# VCFAA_v2.net
KiCad netlist of a schematic drawn in EAGLE
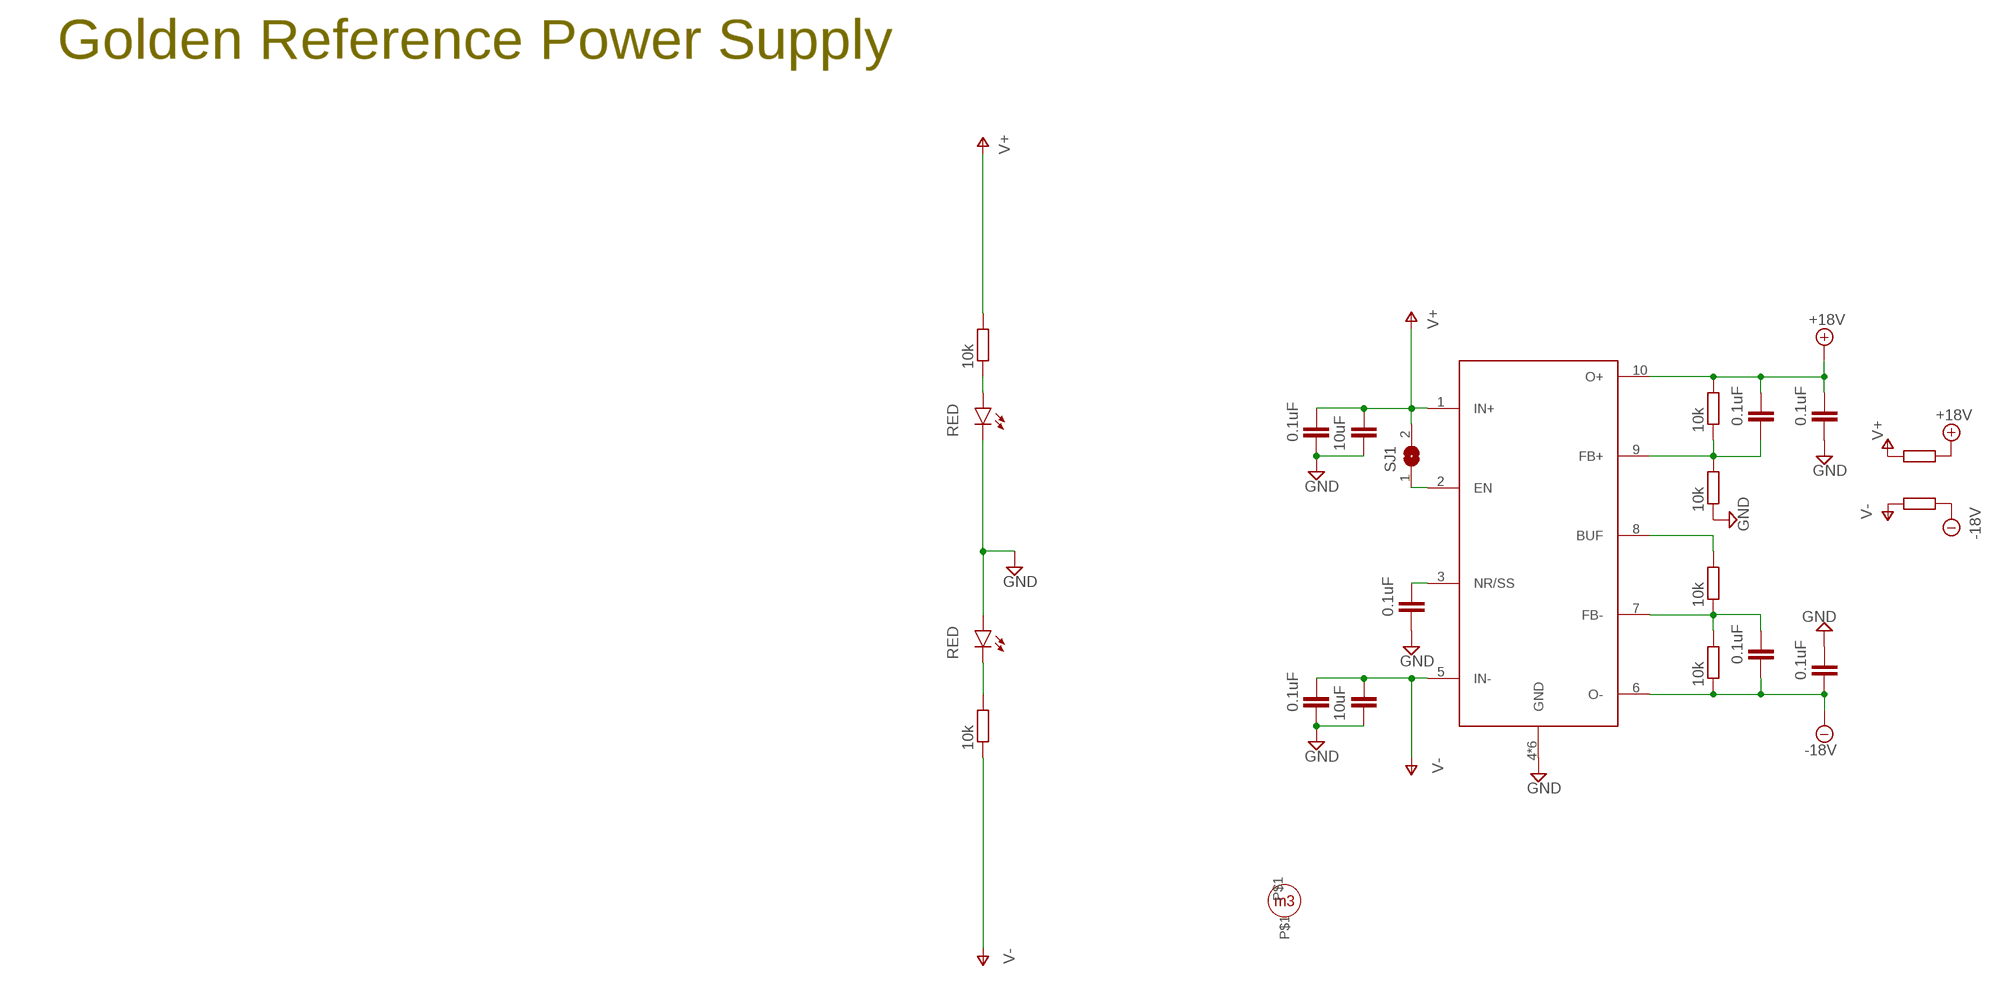
[diagram p0: schematic, sheet 1]
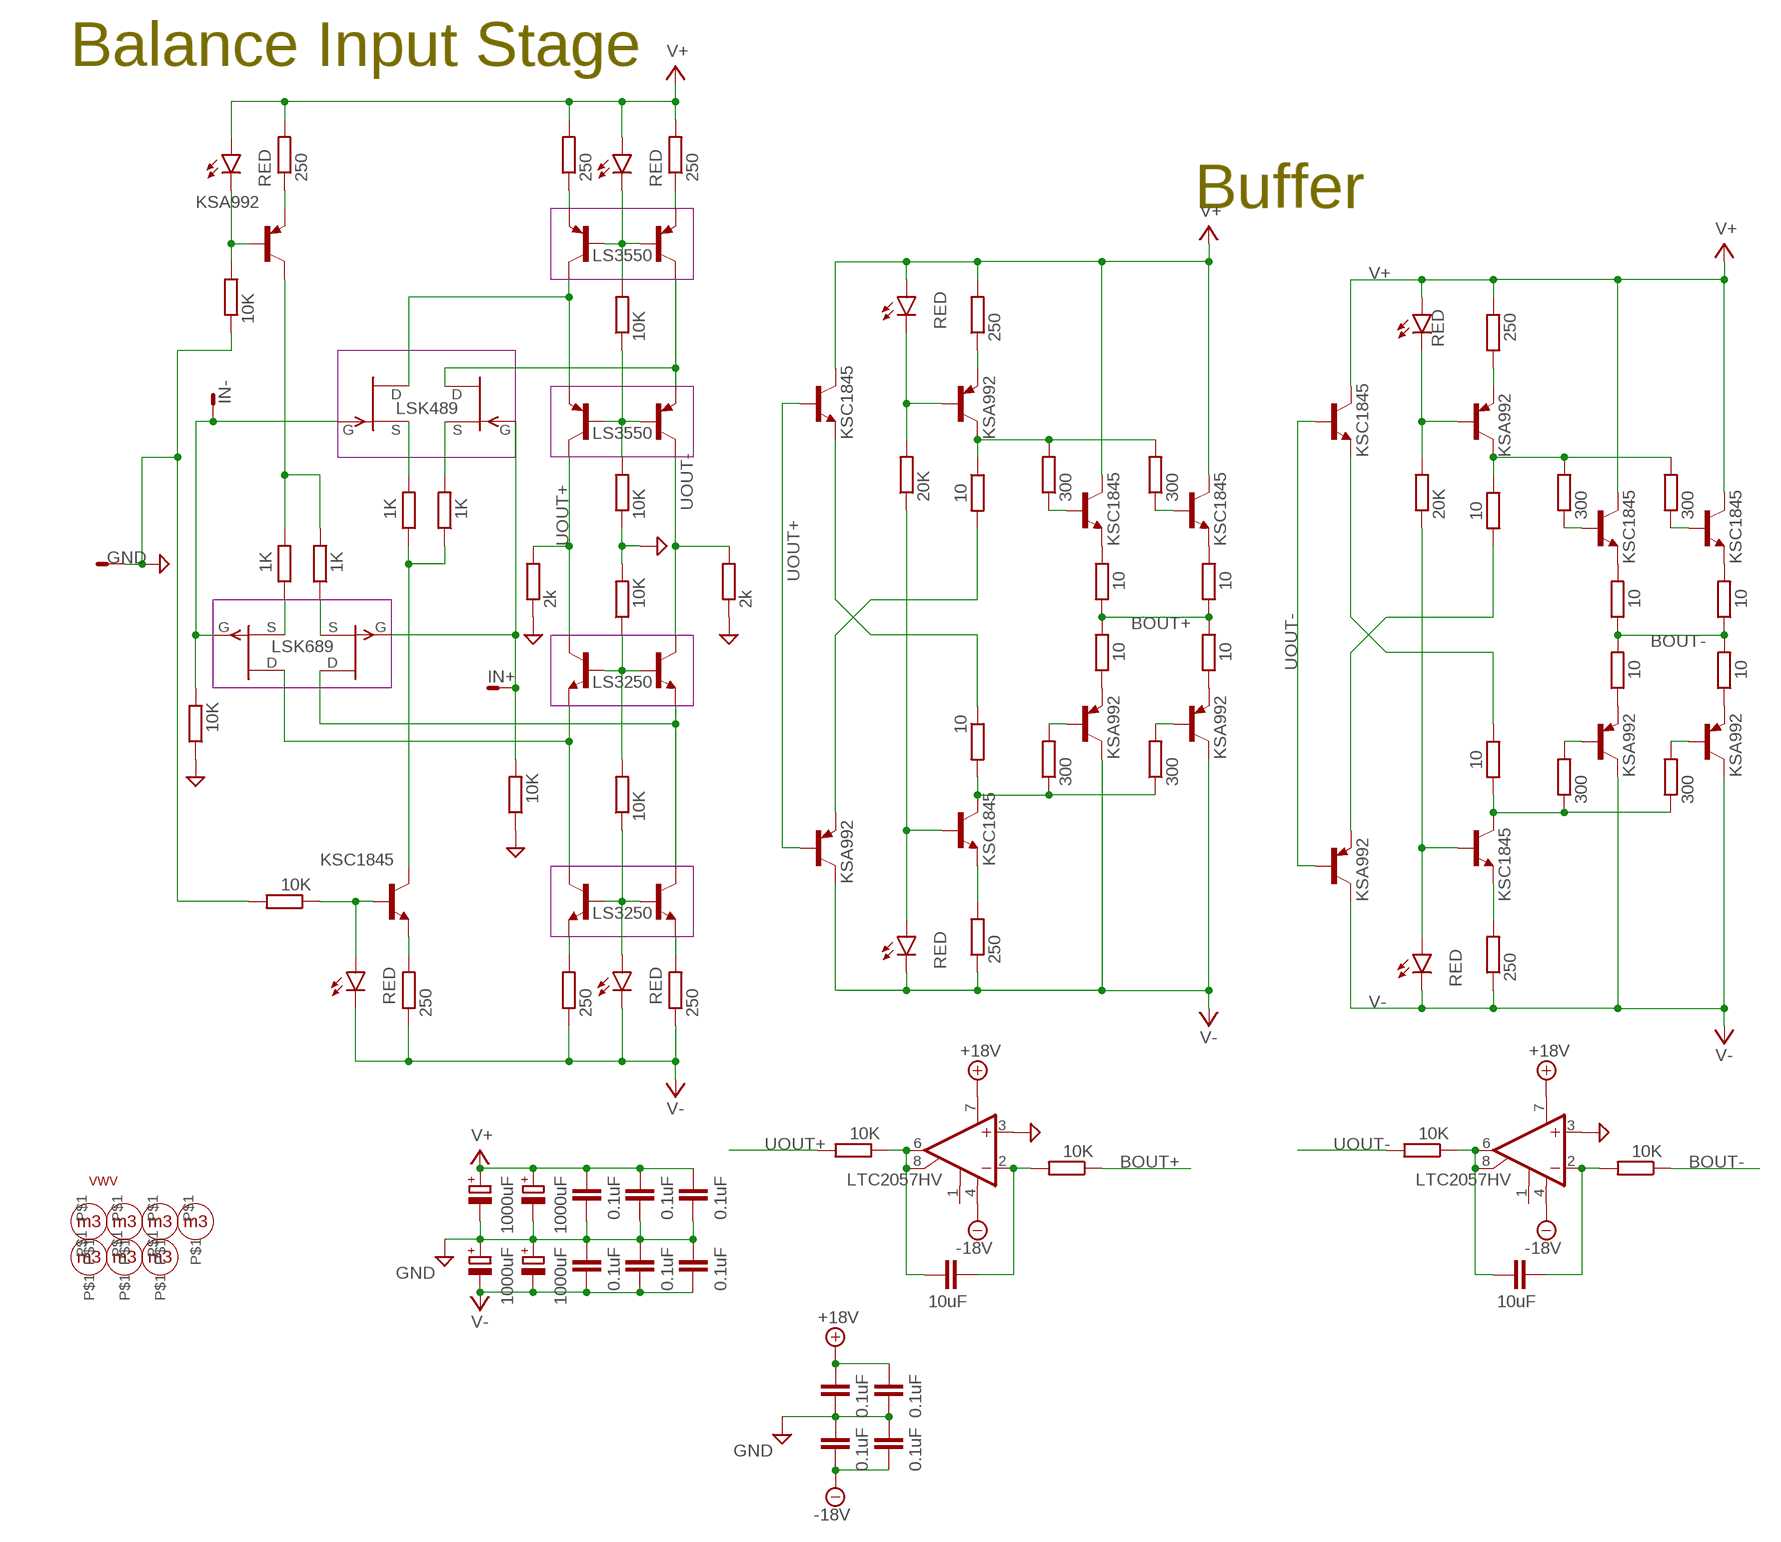
[diagram p1: schematic, sheet 2]
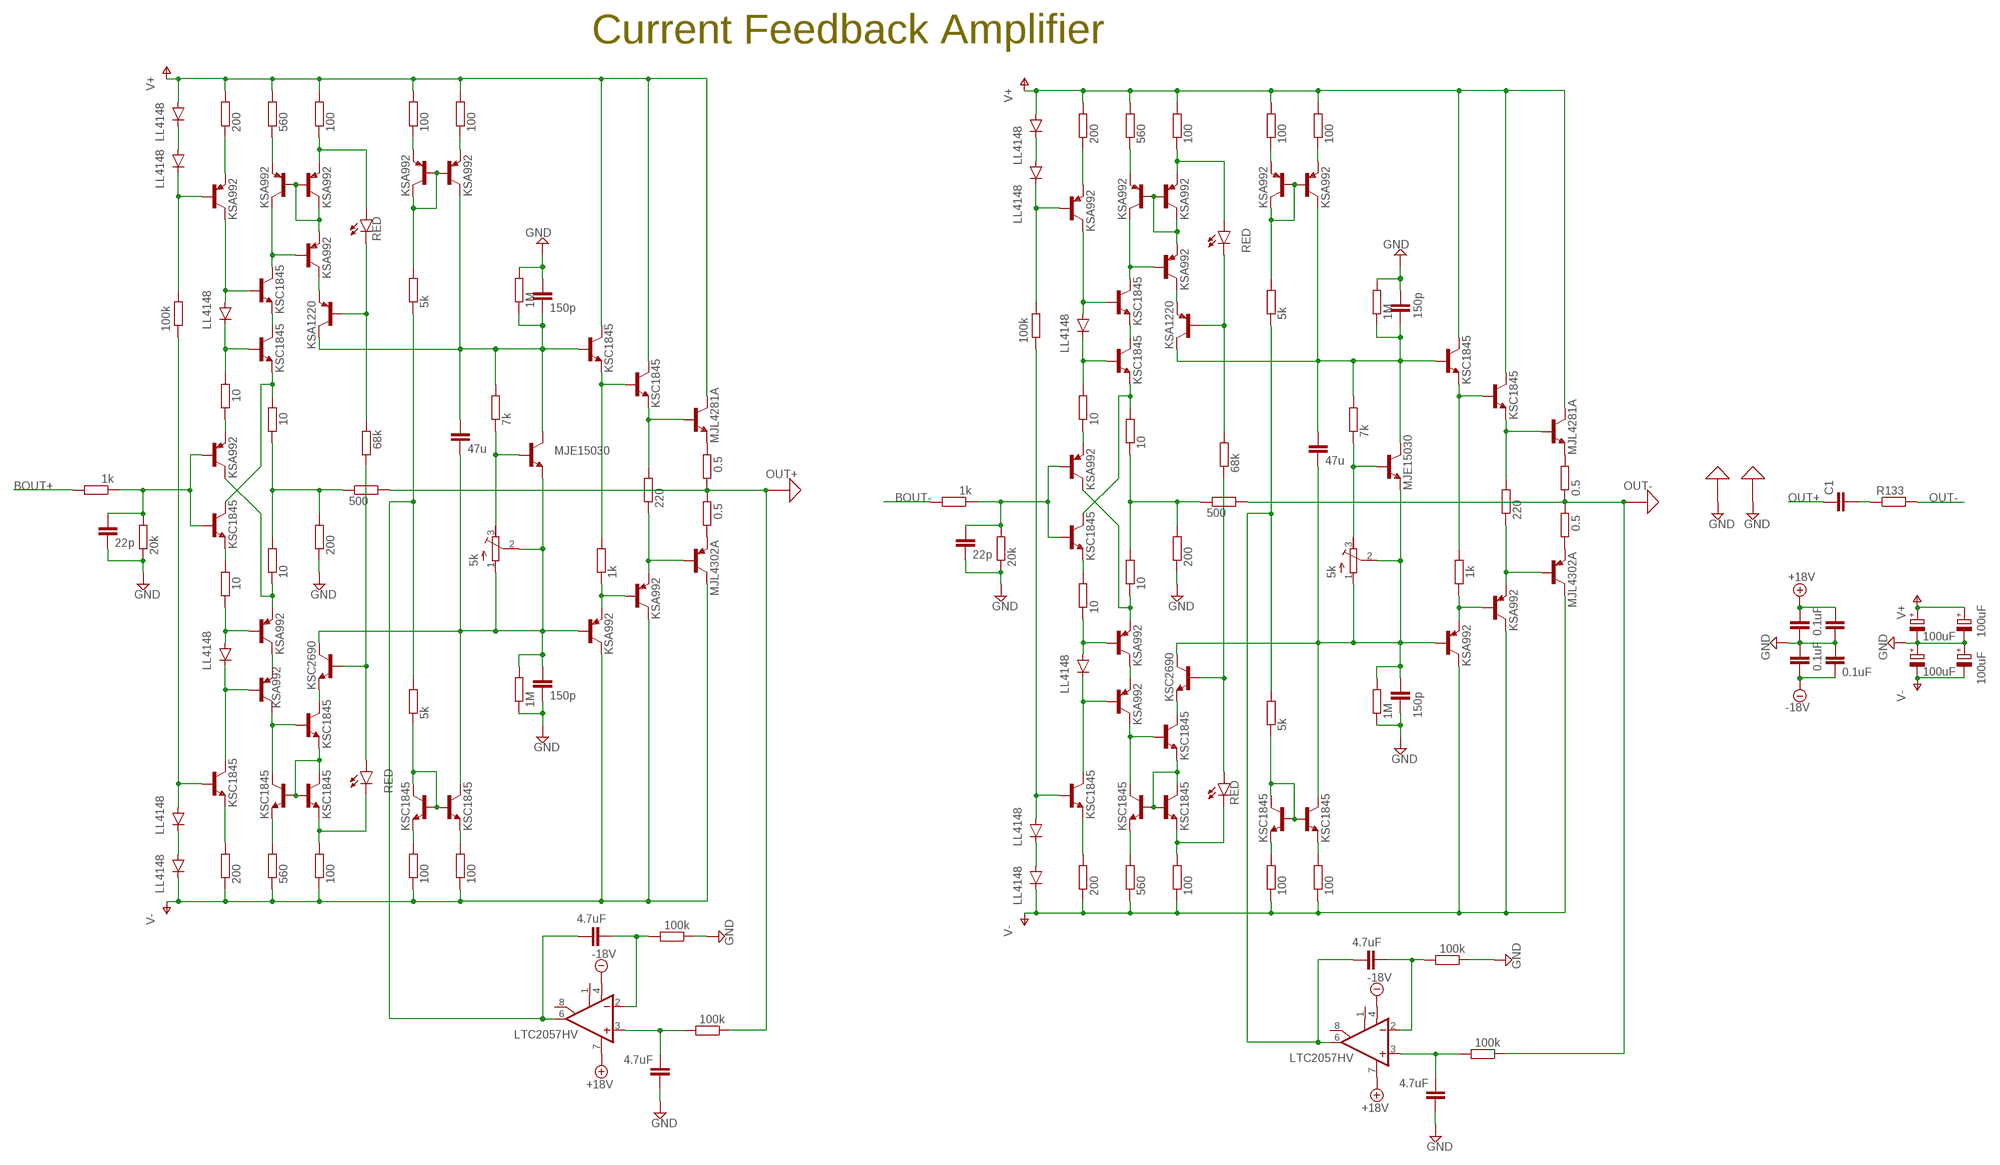
[diagram p2: schematic, sheet 3]

(export (version "E")
  (design (tool "Eeschema 10.0.6"))
  (components
    (comp (ref "C2")
      (value "0.1uF")
      (footprint "eagle-import:C0805")
      (libsource (lib "eagle-import") (part "C-EUC0805"))
    )
    (comp (ref "C65")
      (value "10uF")
      (footprint "eagle-import:C1206")
      (libsource (lib "eagle-import") (part "C-EUC1206"))
    )
    (comp (ref "C66")
      (value "10uF")
      (footprint "eagle-import:C1206")
      (libsource (lib "eagle-import") (part "C-EUC1206"))
    )
    (comp (ref "C67")
      (value "0.1uF")
      (footprint "eagle-import:C0805")
      (libsource (lib "eagle-import") (part "C-EUC0805"))
    )
    (comp (ref "C68")
      (value "0.1uF")
      (footprint "eagle-import:C0805")
      (libsource (lib "eagle-import") (part "C-EUC0805"))
    )
    (comp (ref "C69")
      (value "0.1uF")
      (footprint "eagle-import:C0805")
      (libsource (lib "eagle-import") (part "C-EUC0805"))
    )
    (comp (ref "C70")
      (value "0.1uF")
      (footprint "eagle-import:C0805")
      (libsource (lib "eagle-import") (part "C-EUC0805"))
    )
    (comp (ref "C71")
      (value "0.1uF")
      (footprint "eagle-import:C0805")
      (libsource (lib "eagle-import") (part "C-EUC0805"))
    )
    (comp (ref "C72")
      (value "0.1uF")
      (footprint "eagle-import:C0805")
      (libsource (lib "eagle-import") (part "C-EUC0805"))
    )
    (comp (ref "H8")
      (value "HOLE")
      (footprint "eagle-import:M3_HOLE")
      (libsource (lib "eagle-import") (part "HOLE"))
    )
    (comp (ref "LED17")
      (value "RED")
      (footprint "eagle-import:LED_SML1206")
      (libsource (lib "eagle-import") (part "LEDVWV1206"))
    )
    (comp (ref "LED18")
      (value "RED")
      (footprint "eagle-import:LED_SML1206")
      (libsource (lib "eagle-import") (part "LEDVWV1206"))
    )
    (comp (ref "R131")
      (value "10k")
      (footprint "eagle-import:MINI_MELF-0204W")
      (libsource (lib "eagle-import") (part "R-EU_MELF0204W"))
    )
    (comp (ref "R132")
      (value "10k")
      (footprint "eagle-import:MINI_MELF-0204W")
      (libsource (lib "eagle-import") (part "R-EU_MELF0204W"))
    )
    (comp (ref "R136")
      (value "10k")
      (footprint "eagle-import:MINI_MELF-0204W")
      (libsource (lib "eagle-import") (part "R-EU_MELF0204W"))
    )
    (comp (ref "R137")
      (value "10k")
      (footprint "eagle-import:MINI_MELF-0204W")
      (libsource (lib "eagle-import") (part "R-EU_MELF0204W"))
    )
    (comp (ref "R138")
      (value "10k")
      (footprint "eagle-import:MINI_MELF-0204W")
      (libsource (lib "eagle-import") (part "R-EU_MELF0204W"))
    )
    (comp (ref "R139")
      (value "10k")
      (footprint "eagle-import:MINI_MELF-0204W")
      (libsource (lib "eagle-import") (part "R-EU_MELF0204W"))
    )
    (comp (ref "R140")
      (value "10k")
      (footprint "eagle-import:MINI_MELF-0204W")
      (libsource (lib "eagle-import") (part "R-EU_MELF0204W"))
    )
    (comp (ref "R141")
      (value "10k")
      (footprint "eagle-import:MINI_MELF-0204W")
      (libsource (lib "eagle-import") (part "R-EU_MELF0204W"))
    )
    (comp (ref "SJ1") (value "SJ") (footprint "eagle-import:SJ") (libsource (lib "eagle-import") (part "SJ")))
    (comp (ref "U$5")
      (value "TPS7A39WSON10-7A39")
      (footprint "eagle-import:SON50P300X300X80-11T165X240N")
      (libsource (lib "eagle-import") (part "TPS7A39WSON10-7A39"))
    )
    (comp (ref "C1")
      (value "C-EUECWU-V")
      (footprint "eagle-import:ECHU-Y")
      (libsource (lib "eagle-import") (part "C-EUECWU-V"))
    )
    (comp (ref "C17")
      (value "22p")
      (footprint "eagle-import:C0805")
      (fields (field (name "SPICEPREFIX") "C"))
      (libsource (lib "eagle-import") (part "C-EUC0805"))
    )
    (comp (ref "C18")
      (value "47u")
      (footprint "eagle-import:C1210")
      (fields (field (name "SPICEPREFIX") "C"))
      (libsource (lib "eagle-import") (part "C-EUC1210"))
    )
    (comp (ref "C19")
      (value "150p")
      (footprint "eagle-import:C0805")
      (fields (field (name "SPICEPREFIX") "C"))
      (libsource (lib "eagle-import") (part "C-EUC0805"))
    )
    (comp (ref "C20")
      (value "150p")
      (footprint "eagle-import:C0805")
      (fields (field (name "SPICEPREFIX") "C"))
      (libsource (lib "eagle-import") (part "C-EUC0805"))
    )
    (comp (ref "C21")
      (value "4.7uF")
      (footprint "eagle-import:C1210")
      (fields (field (name "SPICEPREFIX") "C"))
      (libsource (lib "eagle-import") (part "C-EUC1210"))
    )
    (comp (ref "C22")
      (value "4.7uF")
      (footprint "eagle-import:C1210")
      (fields (field (name "SPICEPREFIX") "C"))
      (libsource (lib "eagle-import") (part "C-EUC1210"))
    )
    (comp (ref "C23")
      (value "0.1uF")
      (footprint "eagle-import:C0603K")
      (libsource (lib "eagle-import") (part "C-EUC0603K"))
    )
    (comp (ref "C24")
      (value "0.1uF")
      (footprint "eagle-import:C0603K")
      (libsource (lib "eagle-import") (part "C-EUC0603K"))
    )
    (comp (ref "C25")
      (value "100uF")
      (footprint "eagle-import:E5-8,5")
      (libsource (lib "eagle-import") (part "CPOL-EUE5-8.5"))
    )
    (comp (ref "C26")
      (value "100uF")
      (footprint "eagle-import:E5-8,5")
      (libsource (lib "eagle-import") (part "CPOL-EUE5-8.5"))
    )
    (comp (ref "C27")
      (value "22p")
      (footprint "eagle-import:C0805")
      (fields (field (name "SPICEPREFIX") "C"))
      (libsource (lib "eagle-import") (part "C-EUC0805"))
    )
    (comp (ref "C28")
      (value "47u")
      (footprint "eagle-import:C1210")
      (fields (field (name "SPICEPREFIX") "C"))
      (libsource (lib "eagle-import") (part "C-EUC1210"))
    )
    (comp (ref "C29")
      (value "150p")
      (footprint "eagle-import:C0805")
      (fields (field (name "SPICEPREFIX") "C"))
      (libsource (lib "eagle-import") (part "C-EUC0805"))
    )
    (comp (ref "C30")
      (value "150p")
      (footprint "eagle-import:C0805")
      (fields (field (name "SPICEPREFIX") "C"))
      (libsource (lib "eagle-import") (part "C-EUC0805"))
    )
    (comp (ref "C31")
      (value "4.7uF")
      (footprint "eagle-import:C1210")
      (fields (field (name "SPICEPREFIX") "C"))
      (libsource (lib "eagle-import") (part "C-EUC1210"))
    )
    (comp (ref "C32")
      (value "4.7uF")
      (footprint "eagle-import:C1210")
      (fields (field (name "SPICEPREFIX") "C"))
      (libsource (lib "eagle-import") (part "C-EUC1210"))
    )
    (comp (ref "C33")
      (value "0.1uF")
      (footprint "eagle-import:C0603K")
      (libsource (lib "eagle-import") (part "C-EUC0603K"))
    )
    (comp (ref "C34")
      (value "0.1uF")
      (footprint "eagle-import:C0603K")
      (libsource (lib "eagle-import") (part "C-EUC0603K"))
    )
    (comp (ref "C35")
      (value "100uF")
      (footprint "eagle-import:E5-8,5")
      (libsource (lib "eagle-import") (part "CPOL-EUE5-8.5"))
    )
    (comp (ref "C36")
      (value "100uF")
      (footprint "eagle-import:E5-8,5")
      (libsource (lib "eagle-import") (part "CPOL-EUE5-8.5"))
    )
    (comp (ref "D1")
      (value "LL4148")
      (footprint "eagle-import:SOD80C")
      (fields (field (name "SPICEPREFIX") "D"))
      (libsource (lib "eagle-import") (part "DIODE-SOD80C"))
    )
    (comp (ref "D2")
      (value "LL4148")
      (footprint "eagle-import:SOD80C")
      (fields (field (name "SPICEPREFIX") "D"))
      (libsource (lib "eagle-import") (part "DIODE-SOD80C"))
    )
    (comp (ref "D3")
      (value "LL4148")
      (footprint "eagle-import:SOD80C")
      (fields (field (name "SPICEPREFIX") "D"))
      (libsource (lib "eagle-import") (part "DIODE-SOD80C"))
    )
    (comp (ref "D4")
      (value "LL4148")
      (footprint "eagle-import:SOD80C")
      (fields (field (name "SPICEPREFIX") "D"))
      (libsource (lib "eagle-import") (part "DIODE-SOD80C"))
    )
    (comp (ref "D5")
      (value "LL4148")
      (footprint "eagle-import:SOD80C")
      (fields (field (name "SPICEPREFIX") "D"))
      (libsource (lib "eagle-import") (part "DIODE-SOD80C"))
    )
    (comp (ref "D6")
      (value "LL4148")
      (footprint "eagle-import:SOD80C")
      (fields (field (name "SPICEPREFIX") "D"))
      (libsource (lib "eagle-import") (part "DIODE-SOD80C"))
    )
    (comp (ref "D7")
      (value "LL4148")
      (footprint "eagle-import:SOD80C")
      (fields (field (name "SPICEPREFIX") "D"))
      (libsource (lib "eagle-import") (part "DIODE-SOD80C"))
    )
    (comp (ref "D8")
      (value "LL4148")
      (footprint "eagle-import:SOD80C")
      (fields (field (name "SPICEPREFIX") "D"))
      (libsource (lib "eagle-import") (part "DIODE-SOD80C"))
    )
    (comp (ref "D9")
      (value "LL4148")
      (footprint "eagle-import:SOD80C")
      (fields (field (name "SPICEPREFIX") "D"))
      (libsource (lib "eagle-import") (part "DIODE-SOD80C"))
    )
    (comp (ref "D10")
      (value "LL4148")
      (footprint "eagle-import:SOD80C")
      (fields (field (name "SPICEPREFIX") "D"))
      (libsource (lib "eagle-import") (part "DIODE-SOD80C"))
    )
    (comp (ref "D11")
      (value "LL4148")
      (footprint "eagle-import:SOD80C")
      (fields (field (name "SPICEPREFIX") "D"))
      (libsource (lib "eagle-import") (part "DIODE-SOD80C"))
    )
    (comp (ref "D12")
      (value "LL4148")
      (footprint "eagle-import:SOD80C")
      (fields (field (name "SPICEPREFIX") "D"))
      (libsource (lib "eagle-import") (part "DIODE-SOD80C"))
    )
    (comp (ref "IC3")
      (value "LTC2057HV")
      (footprint "eagle-import:SOIC8")
      (libsource (lib "eagle-import") (part "LT10S837I"))
    )
    (comp (ref "IC4")
      (value "LTC2057HV")
      (footprint "eagle-import:SOIC8")
      (libsource (lib "eagle-import") (part "LT10S837I"))
    )
    (comp (ref "LED9")
      (value "RED")
      (footprint "eagle-import:LED_SML1206")
      (fields (field (name "SPICEPREFIX") "D"))
      (libsource (lib "eagle-import") (part "LEDVWV1206"))
    )
    (comp (ref "LED10")
      (value "RED")
      (footprint "eagle-import:LED_SML1206")
      (fields (field (name "SPICEPREFIX") "D"))
      (libsource (lib "eagle-import") (part "LEDVWV1206"))
    )
    (comp (ref "LED11")
      (value "RED")
      (footprint "eagle-import:LED_SML1206")
      (fields (field (name "SPICEPREFIX") "D"))
      (libsource (lib "eagle-import") (part "LEDVWV1206"))
    )
    (comp (ref "LED12")
      (value "RED")
      (footprint "eagle-import:LED_SML1206")
      (fields (field (name "SPICEPREFIX") "D"))
      (libsource (lib "eagle-import") (part "LEDVWV1206"))
    )
    (comp (ref "PAD1")
      (value "PAD")
      (footprint "eagle-import:PAD-16")
      (libsource (lib "eagle-import") (part "PAD"))
    )
    (comp (ref "PAD2")
      (value "PAD")
      (footprint "eagle-import:PAD-16")
      (libsource (lib "eagle-import") (part "PAD"))
    )
    (comp (ref "PAD3")
      (value "PAD")
      (footprint "eagle-import:PAD-16")
      (libsource (lib "eagle-import") (part "PAD"))
    )
    (comp (ref "PAD4")
      (value "PAD")
      (footprint "eagle-import:PAD-16")
      (libsource (lib "eagle-import") (part "PAD"))
    )
    (comp (ref "Q25")
      (value "KSA992")
      (footprint "eagle-import:TRANSISTOR_TO92-ECB_P")
      (fields (field (name "SPICEPREFIX") "Q"))
      (libsource (lib "eagle-import") (part "BJT_PNPKSA992"))
    )
    (comp (ref "Q26")
      (value "KSA992")
      (footprint "eagle-import:TRANSISTOR_TO92-ECB_P")
      (fields (field (name "SPICEPREFIX") "Q"))
      (libsource (lib "eagle-import") (part "BJT_PNPKSA992"))
    )
    (comp (ref "Q27")
      (value "KSC1845")
      (footprint "eagle-import:TRANSISTOR_TO92-ECB_N")
      (fields (field (name "SPICEPREFIX") "Q"))
      (libsource (lib "eagle-import") (part "BJT_NPNKSC1845"))
    )
    (comp (ref "Q28")
      (value "KSC1845")
      (footprint "eagle-import:TRANSISTOR_TO92-ECB_N")
      (fields (field (name "SPICEPREFIX") "Q"))
      (libsource (lib "eagle-import") (part "BJT_NPNKSC1845"))
    )
    (comp (ref "Q29")
      (value "KSC1845")
      (footprint "eagle-import:TRANSISTOR_TO92-ECB_N")
      (fields (field (name "SPICEPREFIX") "Q"))
      (libsource (lib "eagle-import") (part "BJT_NPNKSC1845"))
    )
    (comp (ref "Q30")
      (value "KSC1845")
      (footprint "eagle-import:TRANSISTOR_TO92-ECB_N")
      (fields (field (name "SPICEPREFIX") "Q"))
      (libsource (lib "eagle-import") (part "BJT_NPNKSC1845"))
    )
    (comp (ref "Q31")
      (value "KSA992")
      (footprint "eagle-import:TRANSISTOR_TO92-ECB_P")
      (fields (field (name "SPICEPREFIX") "Q"))
      (libsource (lib "eagle-import") (part "BJT_PNPKSA992"))
    )
    (comp (ref "Q32")
      (value "KSA992")
      (footprint "eagle-import:TRANSISTOR_TO92-ECB_P")
      (fields (field (name "SPICEPREFIX") "Q"))
      (libsource (lib "eagle-import") (part "BJT_PNPKSA992"))
    )
    (comp (ref "Q33")
      (value "KSA992")
      (footprint "eagle-import:TRANSISTOR_TO92-ECB_P")
      (fields (field (name "SPICEPREFIX") "Q"))
      (libsource (lib "eagle-import") (part "BJT_PNPKSA992"))
    )
    (comp (ref "Q34")
      (value "KSC1845")
      (footprint "eagle-import:TRANSISTOR_TO92-ECB_N")
      (fields (field (name "SPICEPREFIX") "Q"))
      (libsource (lib "eagle-import") (part "BJT_NPNKSC1845"))
    )
    (comp (ref "Q35")
      (value "KSA992")
      (footprint "eagle-import:TRANSISTOR_TO92-ECB_P")
      (fields (field (name "SPICEPREFIX") "Q"))
      (libsource (lib "eagle-import") (part "BJT_PNPKSA992"))
    )
    (comp (ref "Q36")
      (value "KSA992")
      (footprint "eagle-import:TRANSISTOR_TO92-ECB_P")
      (fields (field (name "SPICEPREFIX") "Q"))
      (libsource (lib "eagle-import") (part "BJT_PNPKSA992"))
    )
    (comp (ref "Q37")
      (value "KSC1845")
      (footprint "eagle-import:TRANSISTOR_TO92-ECB_N")
      (fields (field (name "SPICEPREFIX") "Q"))
      (libsource (lib "eagle-import") (part "BJT_NPNKSC1845"))
    )
    (comp (ref "Q38")
      (value "KSC1845")
      (footprint "eagle-import:TRANSISTOR_TO92-ECB_N")
      (fields (field (name "SPICEPREFIX") "Q"))
      (libsource (lib "eagle-import") (part "BJT_NPNKSC1845"))
    )
    (comp (ref "Q39")
      (value "KSA1220")
      (footprint "eagle-import:TRANSISTOR_TO126_P")
      (fields (field (name "SPICEPREFIX") "Q"))
      (libsource (lib "eagle-import") (part "BJT_PNPKSA1220"))
    )
    (comp (ref "Q40")
      (value "KSC2690")
      (footprint "eagle-import:TRANSISTOR_TO126_N")
      (fields (field (name "SPICEPREFIX") "Q"))
      (libsource (lib "eagle-import") (part "BJT_NPNKSC2690"))
    )
    (comp (ref "Q41")
      (value "KSA992")
      (footprint "eagle-import:TRANSISTOR_TO92-ECB_P")
      (fields (field (name "SPICEPREFIX") "Q"))
      (libsource (lib "eagle-import") (part "BJT_PNPKSA992"))
    )
    (comp (ref "Q42")
      (value "KSC1845")
      (footprint "eagle-import:TRANSISTOR_TO92-ECB_N")
      (fields (field (name "SPICEPREFIX") "Q"))
      (libsource (lib "eagle-import") (part "BJT_NPNKSC1845"))
    )
    (comp (ref "Q43")
      (value "KSA992")
      (footprint "eagle-import:TRANSISTOR_TO92-ECB_P")
      (fields (field (name "SPICEPREFIX") "Q"))
      (libsource (lib "eagle-import") (part "BJT_PNPKSA992"))
    )
    (comp (ref "Q44")
      (value "KSC1845")
      (footprint "eagle-import:TRANSISTOR_TO92-ECB_N")
      (fields (field (name "SPICEPREFIX") "Q"))
      (libsource (lib "eagle-import") (part "BJT_NPNKSC1845"))
    )
    (comp (ref "Q45")
      (value "MJE15030")
      (footprint "eagle-import:TRANSISTOR_TO220_BCE_N")
      (fields (field (name "SPICEPREFIX") "Q"))
      (libsource (lib "eagle-import") (part "BJT_NPNMJE15030"))
    )
    (comp (ref "Q46")
      (value "KSC1845")
      (footprint "eagle-import:TRANSISTOR_TO92-ECB_N")
      (fields (field (name "SPICEPREFIX") "Q"))
      (libsource (lib "eagle-import") (part "BJT_NPNKSC1845"))
    )
    (comp (ref "Q47")
      (value "KSA992")
      (footprint "eagle-import:TRANSISTOR_TO92-ECB_P")
      (fields (field (name "SPICEPREFIX") "Q"))
      (libsource (lib "eagle-import") (part "BJT_PNPKSA992"))
    )
    (comp (ref "Q48")
      (value "KSC1845")
      (footprint "eagle-import:TRANSISTOR_TO92-ECB_N")
      (fields (field (name "SPICEPREFIX") "Q"))
      (libsource (lib "eagle-import") (part "BJT_NPNKSC1845"))
    )
    (comp (ref "Q49")
      (value "KSA992")
      (footprint "eagle-import:TRANSISTOR_TO92-ECB_P")
      (fields (field (name "SPICEPREFIX") "Q"))
      (libsource (lib "eagle-import") (part "BJT_PNPKSA992"))
    )
    (comp (ref "Q50")
      (value "MJL4281A")
      (footprint "eagle-import:TRANSISTOR_TO247_BCE_N")
      (fields (field (name "SPICEPREFIX") "Q"))
      (libsource (lib "eagle-import") (part "BJT_NPNMJL4281"))
    )
    (comp (ref "Q51")
      (value "MJL4302A")
      (footprint "eagle-import:TRANSISTOR_TO247_BCE_P")
      (fields (field (name "SPICEPREFIX") "Q"))
      (libsource (lib "eagle-import") (part "BJT_PNPMJL4302"))
    )
    (comp (ref "Q52")
      (value "KSA992")
      (footprint "eagle-import:TRANSISTOR_TO92-ECB_P")
      (fields (field (name "SPICEPREFIX") "Q"))
      (libsource (lib "eagle-import") (part "BJT_PNPKSA992"))
    )
    (comp (ref "Q53")
      (value "KSA992")
      (footprint "eagle-import:TRANSISTOR_TO92-ECB_P")
      (fields (field (name "SPICEPREFIX") "Q"))
      (libsource (lib "eagle-import") (part "BJT_PNPKSA992"))
    )
    (comp (ref "Q54")
      (value "KSC1845")
      (footprint "eagle-import:TRANSISTOR_TO92-ECB_N")
      (fields (field (name "SPICEPREFIX") "Q"))
      (libsource (lib "eagle-import") (part "BJT_NPNKSC1845"))
    )
    (comp (ref "Q55")
      (value "KSC1845")
      (footprint "eagle-import:TRANSISTOR_TO92-ECB_N")
      (fields (field (name "SPICEPREFIX") "Q"))
      (libsource (lib "eagle-import") (part "BJT_NPNKSC1845"))
    )
    (comp (ref "Q56")
      (value "KSC1845")
      (footprint "eagle-import:TRANSISTOR_TO92-ECB_N")
      (fields (field (name "SPICEPREFIX") "Q"))
      (libsource (lib "eagle-import") (part "BJT_NPNKSC1845"))
    )
    (comp (ref "Q57")
      (value "KSC1845")
      (footprint "eagle-import:TRANSISTOR_TO92-ECB_N")
      (fields (field (name "SPICEPREFIX") "Q"))
      (libsource (lib "eagle-import") (part "BJT_NPNKSC1845"))
    )
    (comp (ref "Q58")
      (value "KSA992")
      (footprint "eagle-import:TRANSISTOR_TO92-ECB_P")
      (fields (field (name "SPICEPREFIX") "Q"))
      (libsource (lib "eagle-import") (part "BJT_PNPKSA992"))
    )
    (comp (ref "Q59")
      (value "KSA992")
      (footprint "eagle-import:TRANSISTOR_TO92-ECB_P")
      (fields (field (name "SPICEPREFIX") "Q"))
      (libsource (lib "eagle-import") (part "BJT_PNPKSA992"))
    )
    (comp (ref "Q60")
      (value "KSA992")
      (footprint "eagle-import:TRANSISTOR_TO92-ECB_P")
      (fields (field (name "SPICEPREFIX") "Q"))
      (libsource (lib "eagle-import") (part "BJT_PNPKSA992"))
    )
    (comp (ref "Q61")
      (value "KSC1845")
      (footprint "eagle-import:TRANSISTOR_TO92-ECB_N")
      (fields (field (name "SPICEPREFIX") "Q"))
      (libsource (lib "eagle-import") (part "BJT_NPNKSC1845"))
    )
    (comp (ref "Q62")
      (value "KSA992")
      (footprint "eagle-import:TRANSISTOR_TO92-ECB_P")
      (fields (field (name "SPICEPREFIX") "Q"))
      (libsource (lib "eagle-import") (part "BJT_PNPKSA992"))
    )
    (comp (ref "Q63")
      (value "KSA992")
      (footprint "eagle-import:TRANSISTOR_TO92-ECB_P")
      (fields (field (name "SPICEPREFIX") "Q"))
      (libsource (lib "eagle-import") (part "BJT_PNPKSA992"))
    )
    (comp (ref "Q64")
      (value "KSC1845")
      (footprint "eagle-import:TRANSISTOR_TO92-ECB_N")
      (fields (field (name "SPICEPREFIX") "Q"))
      (libsource (lib "eagle-import") (part "BJT_NPNKSC1845"))
    )
    (comp (ref "Q65")
      (value "KSC1845")
      (footprint "eagle-import:TRANSISTOR_TO92-ECB_N")
      (fields (field (name "SPICEPREFIX") "Q"))
      (libsource (lib "eagle-import") (part "BJT_NPNKSC1845"))
    )
    (comp (ref "Q66")
      (value "KSA1220")
      (footprint "eagle-import:TRANSISTOR_TO126_P")
      (fields (field (name "SPICEPREFIX") "Q"))
      (libsource (lib "eagle-import") (part "BJT_PNPKSA1220"))
    )
    (comp (ref "Q67")
      (value "KSC2690")
      (footprint "eagle-import:TRANSISTOR_TO126_N")
      (fields (field (name "SPICEPREFIX") "Q"))
      (libsource (lib "eagle-import") (part "BJT_NPNKSC2690"))
    )
    (comp (ref "Q68")
      (value "KSA992")
      (footprint "eagle-import:TRANSISTOR_TO92-ECB_P")
      (fields (field (name "SPICEPREFIX") "Q"))
      (libsource (lib "eagle-import") (part "BJT_PNPKSA992"))
    )
    (comp (ref "Q69")
      (value "KSC1845")
      (footprint "eagle-import:TRANSISTOR_TO92-ECB_N")
      (fields (field (name "SPICEPREFIX") "Q"))
      (libsource (lib "eagle-import") (part "BJT_NPNKSC1845"))
    )
    (comp (ref "Q70")
      (value "KSA992")
      (footprint "eagle-import:TRANSISTOR_TO92-ECB_P")
      (fields (field (name "SPICEPREFIX") "Q"))
      (libsource (lib "eagle-import") (part "BJT_PNPKSA992"))
    )
    (comp (ref "Q71")
      (value "KSC1845")
      (footprint "eagle-import:TRANSISTOR_TO92-ECB_N")
      (fields (field (name "SPICEPREFIX") "Q"))
      (libsource (lib "eagle-import") (part "BJT_NPNKSC1845"))
    )
    (comp (ref "Q72")
      (value "MJE15030")
      (footprint "eagle-import:TRANSISTOR_TO220_BCE_N")
      (fields (field (name "SPICEPREFIX") "Q"))
      (libsource (lib "eagle-import") (part "BJT_NPNMJE15030"))
    )
    (comp (ref "Q73")
      (value "KSC1845")
      (footprint "eagle-import:TRANSISTOR_TO92-ECB_N")
      (fields (field (name "SPICEPREFIX") "Q"))
      (libsource (lib "eagle-import") (part "BJT_NPNKSC1845"))
    )
    (comp (ref "Q74")
      (value "KSA992")
      (footprint "eagle-import:TRANSISTOR_TO92-ECB_P")
      (fields (field (name "SPICEPREFIX") "Q"))
      (libsource (lib "eagle-import") (part "BJT_PNPKSA992"))
    )
    (comp (ref "Q75")
      (value "KSC1845")
      (footprint "eagle-import:TRANSISTOR_TO92-ECB_N")
      (fields (field (name "SPICEPREFIX") "Q"))
      (libsource (lib "eagle-import") (part "BJT_NPNKSC1845"))
    )
    (comp (ref "Q76")
      (value "KSA992")
      (footprint "eagle-import:TRANSISTOR_TO92-ECB_P")
      (fields (field (name "SPICEPREFIX") "Q"))
      (libsource (lib "eagle-import") (part "BJT_PNPKSA992"))
    )
    (comp (ref "Q77")
      (value "MJL4281A")
      (footprint "eagle-import:TRANSISTOR_TO247_BCE_N")
      (fields (field (name "SPICEPREFIX") "Q"))
      (libsource (lib "eagle-import") (part "BJT_NPNMJL4281"))
    )
    (comp (ref "Q78")
      (value "MJL4302A")
      (footprint "eagle-import:TRANSISTOR_TO247_BCE_P")
      (fields (field (name "SPICEPREFIX") "Q"))
      (libsource (lib "eagle-import") (part "BJT_PNPMJL4302"))
    )
    (comp (ref "R51")
      (value "1k")
      (footprint "eagle-import:MINI_MELF-0204W")
      (fields (field (name "SPICEPREFIX") "R"))
      (libsource (lib "eagle-import") (part "R-EU_MELF0204W"))
    )
    (comp (ref "R52")
      (value "20k")
      (footprint "eagle-import:MINI_MELF-0204W")
      (fields (field (name "SPICEPREFIX") "R"))
      (libsource (lib "eagle-import") (part "R-EU_MELF0204W"))
    )
    (comp (ref "R53")
      (value "100k")
      (footprint "eagle-import:MINI_MELF-0204W")
      (fields (field (name "SPICEPREFIX") "R"))
      (libsource (lib "eagle-import") (part "R-EU_MELF0204W"))
    )
    (comp (ref "R54")
      (value "200")
      (footprint "eagle-import:MINI_MELF-0204W")
      (fields (field (name "SPICEPREFIX") "R"))
      (libsource (lib "eagle-import") (part "R-EU_MELF0204W"))
    )
    (comp (ref "R55")
      (value "10")
      (footprint "eagle-import:MINI_MELF-0204W")
      (fields (field (name "SPICEPREFIX") "R"))
      (libsource (lib "eagle-import") (part "R-EU_MELF0204W"))
    )
    (comp (ref "R56")
      (value "10")
      (footprint "eagle-import:MINI_MELF-0204W")
      (fields (field (name "SPICEPREFIX") "R"))
      (libsource (lib "eagle-import") (part "R-EU_MELF0204W"))
    )
    (comp (ref "R57")
      (value "200")
      (footprint "eagle-import:MINI_MELF-0204W")
      (fields (field (name "SPICEPREFIX") "R"))
      (libsource (lib "eagle-import") (part "R-EU_MELF0204W"))
    )
    (comp (ref "R58")
      (value "560")
      (footprint "eagle-import:MINI_MELF-0204W")
      (fields (field (name "SPICEPREFIX") "R"))
      (libsource (lib "eagle-import") (part "R-EU_MELF0204W"))
    )
    (comp (ref "R59")
      (value "10")
      (footprint "eagle-import:MINI_MELF-0204W")
      (fields (field (name "SPICEPREFIX") "R"))
      (libsource (lib "eagle-import") (part "R-EU_MELF0204W"))
    )
    (comp (ref "R60")
      (value "10")
      (footprint "eagle-import:MINI_MELF-0204W")
      (fields (field (name "SPICEPREFIX") "R"))
      (libsource (lib "eagle-import") (part "R-EU_MELF0204W"))
    )
    (comp (ref "R61")
      (value "560")
      (footprint "eagle-import:MINI_MELF-0204W")
      (fields (field (name "SPICEPREFIX") "R"))
      (libsource (lib "eagle-import") (part "R-EU_MELF0204W"))
    )
    (comp (ref "R62")
      (value "100")
      (footprint "eagle-import:MINI_MELF-0204W")
      (fields (field (name "SPICEPREFIX") "R"))
      (libsource (lib "eagle-import") (part "R-EU_MELF0204W"))
    )
    (comp (ref "R63")
      (value "200")
      (footprint "eagle-import:MINI_MELF-0204W")
      (fields (field (name "SPICEPREFIX") "R"))
      (libsource (lib "eagle-import") (part "R-EU_MELF0204W"))
    )
    (comp (ref "R64")
      (value "100")
      (footprint "eagle-import:MINI_MELF-0204W")
      (fields (field (name "SPICEPREFIX") "R"))
      (libsource (lib "eagle-import") (part "R-EU_MELF0204W"))
    )
    (comp (ref "R65")
      (value "68k")
      (footprint "eagle-import:MINI_MELF-0204W")
      (fields (field (name "SPICEPREFIX") "R"))
      (libsource (lib "eagle-import") (part "R-EU_MELF0204W"))
    )
    (comp (ref "R66")
      (value "500")
      (footprint "eagle-import:MINI_MELF-0204W")
      (fields (field (name "SPICEPREFIX") "R"))
      (libsource (lib "eagle-import") (part "R-EU_MELF0204W"))
    )
    (comp (ref "R67")
      (value "100")
      (footprint "eagle-import:MINI_MELF-0204W")
      (fields (field (name "SPICEPREFIX") "R"))
      (libsource (lib "eagle-import") (part "R-EU_MELF0204W"))
    )
    (comp (ref "R68")
      (value "5k")
      (footprint "eagle-import:MINI_MELF-0204W")
      (fields (field (name "SPICEPREFIX") "R"))
      (libsource (lib "eagle-import") (part "R-EU_MELF0204W"))
    )
    (comp (ref "R69")
      (value "5k")
      (footprint "eagle-import:MINI_MELF-0204W")
      (fields (field (name "SPICEPREFIX") "R"))
      (libsource (lib "eagle-import") (part "R-EU_MELF0204W"))
    )
    (comp (ref "R70")
      (value "100")
      (footprint "eagle-import:MINI_MELF-0204W")
      (fields (field (name "SPICEPREFIX") "R"))
      (libsource (lib "eagle-import") (part "R-EU_MELF0204W"))
    )
    (comp (ref "R71")
      (value "100")
      (footprint "eagle-import:MINI_MELF-0204W")
      (fields (field (name "SPICEPREFIX") "R"))
      (libsource (lib "eagle-import") (part "R-EU_MELF0204W"))
    )
    (comp (ref "R72")
      (value "100")
      (footprint "eagle-import:MINI_MELF-0204W")
      (fields (field (name "SPICEPREFIX") "R"))
      (libsource (lib "eagle-import") (part "R-EU_MELF0204W"))
    )
    (comp (ref "R73")
      (value "7k")
      (footprint "eagle-import:MINI_MELF-0204W")
      (fields (field (name "SPICEPREFIX") "R"))
      (libsource (lib "eagle-import") (part "R-EU_MELF0204W"))
    )
    (comp (ref "R74")
      (value "5k")
      (footprint "eagle-import:RTRIM3296W")
      (fields (field (name "SPICEPREFIX") "Z"))
      (libsource (lib "eagle-import") (part "R-TRIMM3296W"))
    )
    (comp (ref "R75")
      (value "1M")
      (footprint "eagle-import:MINI_MELF-0204W")
      (fields (field (name "SPICEPREFIX") "R"))
      (libsource (lib "eagle-import") (part "R-EU_MELF0204W"))
    )
    (comp (ref "R76")
      (value "1M")
      (footprint "eagle-import:MINI_MELF-0204W")
      (fields (field (name "SPICEPREFIX") "R"))
      (libsource (lib "eagle-import") (part "R-EU_MELF0204W"))
    )
    (comp (ref "R77")
      (value "1k")
      (footprint "eagle-import:MINI_MELF-0204W")
      (fields (field (name "SPICEPREFIX") "R"))
      (libsource (lib "eagle-import") (part "R-EU_MELF0204W"))
    )
    (comp (ref "R78")
      (value "220")
      (footprint "eagle-import:MINI_MELF-0204W")
      (fields (field (name "SPICEPREFIX") "R"))
      (libsource (lib "eagle-import") (part "R-EU_MELF0204W"))
    )
    (comp (ref "R79")
      (value "100k")
      (footprint "eagle-import:MINI_MELF-0204W")
      (fields (field (name "SPICEPREFIX") "R"))
      (libsource (lib "eagle-import") (part "R-EU_MELF0204W"))
    )
    (comp (ref "R80")
      (value "0.5")
      (footprint "eagle-import:R2512")
      (fields (field (name "SPICEPREFIX") "R"))
      (libsource (lib "eagle-import") (part "R-EU_R2512"))
    )
    (comp (ref "R81")
      (value "0.5")
      (footprint "eagle-import:R2512")
      (fields (field (name "SPICEPREFIX") "R"))
      (libsource (lib "eagle-import") (part "R-EU_R2512"))
    )
    (comp (ref "R82")
      (value "100k")
      (footprint "eagle-import:MINI_MELF-0204W")
      (fields (field (name "SPICEPREFIX") "R"))
      (libsource (lib "eagle-import") (part "R-EU_MELF0204W"))
    )
    (comp (ref "R83")
      (value "1k")
      (footprint "eagle-import:MINI_MELF-0204W")
      (fields (field (name "SPICEPREFIX") "R"))
      (libsource (lib "eagle-import") (part "R-EU_MELF0204W"))
    )
    (comp (ref "R84")
      (value "20k")
      (footprint "eagle-import:MINI_MELF-0204W")
      (fields (field (name "SPICEPREFIX") "R"))
      (libsource (lib "eagle-import") (part "R-EU_MELF0204W"))
    )
    (comp (ref "R85")
      (value "100k")
      (footprint "eagle-import:MINI_MELF-0204W")
      (fields (field (name "SPICEPREFIX") "R"))
      (libsource (lib "eagle-import") (part "R-EU_MELF0204W"))
    )
    (comp (ref "R86")
      (value "200")
      (footprint "eagle-import:MINI_MELF-0204W")
      (fields (field (name "SPICEPREFIX") "R"))
      (libsource (lib "eagle-import") (part "R-EU_MELF0204W"))
    )
    (comp (ref "R87")
      (value "10")
      (footprint "eagle-import:MINI_MELF-0204W")
      (fields (field (name "SPICEPREFIX") "R"))
      (libsource (lib "eagle-import") (part "R-EU_MELF0204W"))
    )
    (comp (ref "R88")
      (value "10")
      (footprint "eagle-import:MINI_MELF-0204W")
      (fields (field (name "SPICEPREFIX") "R"))
      (libsource (lib "eagle-import") (part "R-EU_MELF0204W"))
    )
    (comp (ref "R89")
      (value "200")
      (footprint "eagle-import:MINI_MELF-0204W")
      (fields (field (name "SPICEPREFIX") "R"))
      (libsource (lib "eagle-import") (part "R-EU_MELF0204W"))
    )
    (comp (ref "R90")
      (value "560")
      (footprint "eagle-import:MINI_MELF-0204W")
      (fields (field (name "SPICEPREFIX") "R"))
      (libsource (lib "eagle-import") (part "R-EU_MELF0204W"))
    )
    (comp (ref "R91")
      (value "10")
      (footprint "eagle-import:MINI_MELF-0204W")
      (fields (field (name "SPICEPREFIX") "R"))
      (libsource (lib "eagle-import") (part "R-EU_MELF0204W"))
    )
    (comp (ref "R92")
      (value "10")
      (footprint "eagle-import:MINI_MELF-0204W")
      (fields (field (name "SPICEPREFIX") "R"))
      (libsource (lib "eagle-import") (part "R-EU_MELF0204W"))
    )
    (comp (ref "R93")
      (value "560")
      (footprint "eagle-import:MINI_MELF-0204W")
      (fields (field (name "SPICEPREFIX") "R"))
      (libsource (lib "eagle-import") (part "R-EU_MELF0204W"))
    )
    (comp (ref "R94")
      (value "100")
      (footprint "eagle-import:MINI_MELF-0204W")
      (fields (field (name "SPICEPREFIX") "R"))
      (libsource (lib "eagle-import") (part "R-EU_MELF0204W"))
    )
    (comp (ref "R95")
      (value "200")
      (footprint "eagle-import:MINI_MELF-0204W")
      (fields (field (name "SPICEPREFIX") "R"))
      (libsource (lib "eagle-import") (part "R-EU_MELF0204W"))
    )
    (comp (ref "R96")
      (value "100")
      (footprint "eagle-import:MINI_MELF-0204W")
      (fields (field (name "SPICEPREFIX") "R"))
      (libsource (lib "eagle-import") (part "R-EU_MELF0204W"))
    )
    (comp (ref "R97")
      (value "68k")
      (footprint "eagle-import:MINI_MELF-0204W")
      (fields (field (name "SPICEPREFIX") "R"))
      (libsource (lib "eagle-import") (part "R-EU_MELF0204W"))
    )
    (comp (ref "R98")
      (value "500")
      (footprint "eagle-import:MINI_MELF-0204W")
      (fields (field (name "SPICEPREFIX") "R"))
      (libsource (lib "eagle-import") (part "R-EU_MELF0204W"))
    )
    (comp (ref "R99")
      (value "100")
      (footprint "eagle-import:MINI_MELF-0204W")
      (fields (field (name "SPICEPREFIX") "R"))
      (libsource (lib "eagle-import") (part "R-EU_MELF0204W"))
    )
    (comp (ref "R100")
      (value "5k")
      (footprint "eagle-import:MINI_MELF-0204W")
      (fields (field (name "SPICEPREFIX") "R"))
      (libsource (lib "eagle-import") (part "R-EU_MELF0204W"))
    )
    (comp (ref "R101")
      (value "5k")
      (footprint "eagle-import:MINI_MELF-0204W")
      (fields (field (name "SPICEPREFIX") "R"))
      (libsource (lib "eagle-import") (part "R-EU_MELF0204W"))
    )
    (comp (ref "R102")
      (value "100")
      (footprint "eagle-import:MINI_MELF-0204W")
      (fields (field (name "SPICEPREFIX") "R"))
      (libsource (lib "eagle-import") (part "R-EU_MELF0204W"))
    )
    (comp (ref "R103")
      (value "100")
      (footprint "eagle-import:MINI_MELF-0204W")
      (fields (field (name "SPICEPREFIX") "R"))
      (libsource (lib "eagle-import") (part "R-EU_MELF0204W"))
    )
    (comp (ref "R104")
      (value "100")
      (footprint "eagle-import:MINI_MELF-0204W")
      (fields (field (name "SPICEPREFIX") "R"))
      (libsource (lib "eagle-import") (part "R-EU_MELF0204W"))
    )
    (comp (ref "R105")
      (value "7k")
      (footprint "eagle-import:MINI_MELF-0204W")
      (fields (field (name "SPICEPREFIX") "R"))
      (libsource (lib "eagle-import") (part "R-EU_MELF0204W"))
    )
    (comp (ref "R106")
      (value "5k")
      (footprint "eagle-import:RTRIM3296W")
      (fields (field (name "SPICEPREFIX") "Z"))
      (libsource (lib "eagle-import") (part "R-TRIMM3296W"))
    )
    (comp (ref "R107")
      (value "1M")
      (footprint "eagle-import:MINI_MELF-0204W")
      (fields (field (name "SPICEPREFIX") "R"))
      (libsource (lib "eagle-import") (part "R-EU_MELF0204W"))
    )
    (comp (ref "R108")
      (value "1M")
      (footprint "eagle-import:MINI_MELF-0204W")
      (fields (field (name "SPICEPREFIX") "R"))
      (libsource (lib "eagle-import") (part "R-EU_MELF0204W"))
    )
    (comp (ref "R109")
      (value "1k")
      (footprint "eagle-import:MINI_MELF-0204W")
      (fields (field (name "SPICEPREFIX") "R"))
      (libsource (lib "eagle-import") (part "R-EU_MELF0204W"))
    )
    (comp (ref "R110")
      (value "220")
      (footprint "eagle-import:MINI_MELF-0204W")
      (fields (field (name "SPICEPREFIX") "R"))
      (libsource (lib "eagle-import") (part "R-EU_MELF0204W"))
    )
    (comp (ref "R111")
      (value "100k")
      (footprint "eagle-import:MINI_MELF-0204W")
      (fields (field (name "SPICEPREFIX") "R"))
      (libsource (lib "eagle-import") (part "R-EU_MELF0204W"))
    )
    (comp (ref "R112")
      (value "0.5")
      (footprint "eagle-import:R2512")
      (fields (field (name "SPICEPREFIX") "R"))
      (libsource (lib "eagle-import") (part "R-EU_R2512"))
    )
    (comp (ref "R113")
      (value "0.5")
      (footprint "eagle-import:R2512")
      (fields (field (name "SPICEPREFIX") "R"))
      (libsource (lib "eagle-import") (part "R-EU_R2512"))
    )
    (comp (ref "R114")
      (value "100k")
      (footprint "eagle-import:MINI_MELF-0204W")
      (fields (field (name "SPICEPREFIX") "R"))
      (libsource (lib "eagle-import") (part "R-EU_MELF0204W"))
    )
    (comp (ref "R133")
      (value "R-EU_R2512")
      (footprint "eagle-import:R2512")
      (libsource (lib "eagle-import") (part "R-EU_R2512"))
    )
    (comp (ref "C3")
      (value "0.1uF")
      (footprint "eagle-import:C0805")
      (libsource (lib "eagle-import") (part "C-EUC0805"))
    )
    (comp (ref "C4")
      (value "0.1uF")
      (footprint "eagle-import:C0805")
      (libsource (lib "eagle-import") (part "C-EUC0805"))
    )
    (comp (ref "C5")
      (value "1000uF")
      (footprint "eagle-import:E7,5-18")
      (libsource (lib "eagle-import") (part "CPOL-EUE7.5-18"))
    )
    (comp (ref "C6")
      (value "1000uF")
      (footprint "eagle-import:E7,5-18")
      (libsource (lib "eagle-import") (part "CPOL-EUE7.5-18"))
    )
    (comp (ref "C7")
      (value "1000uF")
      (footprint "eagle-import:E7,5-18")
      (libsource (lib "eagle-import") (part "CPOL-EUE7.5-18"))
    )
    (comp (ref "C8")
      (value "1000uF")
      (footprint "eagle-import:E7,5-18")
      (libsource (lib "eagle-import") (part "CPOL-EUE7.5-18"))
    )
    (comp (ref "C9")
      (value "0.1uF")
      (footprint "eagle-import:C050-045X075")
      (libsource (lib "eagle-import") (part "C-EU050-045X075"))
    )
    (comp (ref "C10")
      (value "0.1uF")
      (footprint "eagle-import:C050-045X075")
      (libsource (lib "eagle-import") (part "C-EU050-045X075"))
    )
    (comp (ref "C11")
      (value "0.1uF")
      (footprint "eagle-import:C050-045X075")
      (libsource (lib "eagle-import") (part "C-EU050-045X075"))
    )
    (comp (ref "C12")
      (value "0.1uF")
      (footprint "eagle-import:C050-045X075")
      (libsource (lib "eagle-import") (part "C-EU050-045X075"))
    )
    (comp (ref "C13")
      (value "10uF")
      (footprint "eagle-import:C1206")
      (libsource (lib "eagle-import") (part "C-EUC1206"))
    )
    (comp (ref "C14")
      (value "0.1uF")
      (footprint "eagle-import:C0805")
      (libsource (lib "eagle-import") (part "C-EUC0805"))
    )
    (comp (ref "C15")
      (value "0.1uF")
      (footprint "eagle-import:C0805")
      (libsource (lib "eagle-import") (part "C-EUC0805"))
    )
    (comp (ref "C16")
      (value "10uF")
      (footprint "eagle-import:C1206")
      (libsource (lib "eagle-import") (part "C-EUC1206"))
    )
    (comp (ref "C74")
      (value "0.1uF")
      (footprint "eagle-import:C050-045X075")
      (libsource (lib "eagle-import") (part "C-EU050-045X075"))
    )
    (comp (ref "C75")
      (value "0.1uF")
      (footprint "eagle-import:C050-045X075")
      (libsource (lib "eagle-import") (part "C-EU050-045X075"))
    )
    (comp (ref "H1")
      (value "HOLE")
      (footprint "eagle-import:M3_HOLE")
      (libsource (lib "eagle-import") (part "HOLE"))
    )
    (comp (ref "H2")
      (value "HOLE")
      (footprint "eagle-import:M3_HOLE")
      (libsource (lib "eagle-import") (part "HOLE"))
    )
    (comp (ref "H3")
      (value "HOLE")
      (footprint "eagle-import:M3_HOLE")
      (libsource (lib "eagle-import") (part "HOLE"))
    )
    (comp (ref "H4")
      (value "HOLE")
      (footprint "eagle-import:M3_HOLE")
      (libsource (lib "eagle-import") (part "HOLE"))
    )
    (comp (ref "H5")
      (value "HOLE")
      (footprint "eagle-import:M3_HOLE")
      (libsource (lib "eagle-import") (part "HOLE"))
    )
    (comp (ref "H6")
      (value "HOLE")
      (footprint "eagle-import:M3_HOLE")
      (libsource (lib "eagle-import") (part "HOLE"))
    )
    (comp (ref "H7")
      (value "HOLE")
      (footprint "eagle-import:M3_HOLE")
      (libsource (lib "eagle-import") (part "HOLE"))
    )
    (comp (ref "IC1")
      (value "LTC2057HV")
      (footprint "eagle-import:SOIC8")
      (libsource (lib "eagle-import") (part "LT10S807C"))
    )
    (comp (ref "IC2")
      (value "LTC2057HV")
      (footprint "eagle-import:SOIC8")
      (libsource (lib "eagle-import") (part "LT10S807C"))
    )
    (comp (ref "LED1")
      (value "RED")
      (footprint "eagle-import:LED_SML1206")
      (libsource (lib "eagle-import") (part "LEDVWV1206"))
    )
    (comp (ref "LED2")
      (value "RED")
      (footprint "eagle-import:LED_SML1206")
      (fields (field (name "SPICEPREFIX") "D"))
      (libsource (lib "eagle-import") (part "LEDVWV1206"))
    )
    (comp (ref "LED3")
      (value "RED")
      (footprint "eagle-import:LED_SML1206")
      (libsource (lib "eagle-import") (part "LEDVWV1206"))
    )
    (comp (ref "LED4")
      (value "RED")
      (footprint "eagle-import:LED_SML1206")
      (libsource (lib "eagle-import") (part "LEDVWV1206"))
    )
    (comp (ref "LED5")
      (value "RED")
      (footprint "eagle-import:LED_SML1206")
      (libsource (lib "eagle-import") (part "LEDVWV1206"))
    )
    (comp (ref "LED6")
      (value "RED")
      (footprint "eagle-import:LED_SML1206")
      (libsource (lib "eagle-import") (part "LEDVWV1206"))
    )
    (comp (ref "LED7")
      (value "RED")
      (footprint "eagle-import:LED_SML1206")
      (libsource (lib "eagle-import") (part "LEDVWV1206"))
    )
    (comp (ref "LED8")
      (value "RED")
      (footprint "eagle-import:LED_SML1206")
      (libsource (lib "eagle-import") (part "LEDVWV1206"))
    )
    (comp (ref "Q1")
      (value "LSK689")
      (footprint "eagle-import:SOT-23-6")
      (libsource (lib "eagle-import") (part "LSK689"))
    )
    (comp (ref "Q2")
      (value "KSA992")
      (footprint "eagle-import:TRANSISTOR_TO92-ECB_P")
      (libsource (lib "eagle-import") (part "BJT_PNPKSA992"))
    )
    (comp (ref "Q3")
      (value "KSC1845")
      (footprint "eagle-import:TRANSISTOR_TO92-ECB_N")
      (libsource (lib "eagle-import") (part "BJT_NPNKSC1845"))
    )
    (comp (ref "Q4")
      (value "LSK489")
      (footprint "eagle-import:SOT-23-6")
      (libsource (lib "eagle-import") (part "LSK489SOP-6"))
    )
    (comp (ref "Q5")
      (value "LS3550")
      (footprint "eagle-import:SOT-23-6")
      (libsource (lib "eagle-import") (part "LS3550"))
    )
    (comp (ref "Q6")
      (value "LS3250")
      (footprint "eagle-import:SOT-23-6")
      (libsource (lib "eagle-import") (part "LS3250"))
    )
    (comp (ref "Q7")
      (value "LS3250")
      (footprint "eagle-import:SOT-23-6")
      (libsource (lib "eagle-import") (part "LS3250"))
    )
    (comp (ref "Q8")
      (value "LS3550")
      (footprint "eagle-import:SOT-23-6")
      (libsource (lib "eagle-import") (part "LS3550"))
    )
    (comp (ref "Q9")
      (value "KSC1845")
      (footprint "eagle-import:TRANSISTOR_TO92-ECB_N")
      (libsource (lib "eagle-import") (part "BJT_NPNKSC1845"))
    )
    (comp (ref "Q10")
      (value "KSA992")
      (footprint "eagle-import:TRANSISTOR_TO92-ECB_P")
      (libsource (lib "eagle-import") (part "BJT_PNPKSA992"))
    )
    (comp (ref "Q11")
      (value "KSA992")
      (footprint "eagle-import:TRANSISTOR_TO92-ECB_P")
      (libsource (lib "eagle-import") (part "BJT_PNPKSA992"))
    )
    (comp (ref "Q12")
      (value "KSC1845")
      (footprint "eagle-import:TRANSISTOR_TO92-ECB_N")
      (libsource (lib "eagle-import") (part "BJT_NPNKSC1845"))
    )
    (comp (ref "Q13")
      (value "KSC1845")
      (footprint "eagle-import:TRANSISTOR_TO92-ECB_N")
      (libsource (lib "eagle-import") (part "BJT_NPNKSC1845"))
    )
    (comp (ref "Q14")
      (value "KSA992")
      (footprint "eagle-import:TRANSISTOR_TO92-ECB_P")
      (libsource (lib "eagle-import") (part "BJT_PNPKSA992"))
    )
    (comp (ref "Q15")
      (value "KSC1845")
      (footprint "eagle-import:TRANSISTOR_TO92-ECB_N")
      (libsource (lib "eagle-import") (part "BJT_NPNKSC1845"))
    )
    (comp (ref "Q16")
      (value "KSA992")
      (footprint "eagle-import:TRANSISTOR_TO92-ECB_P")
      (libsource (lib "eagle-import") (part "BJT_PNPKSA992"))
    )
    (comp (ref "Q17")
      (value "KSC1845")
      (footprint "eagle-import:TRANSISTOR_TO92-ECB_N")
      (libsource (lib "eagle-import") (part "BJT_NPNKSC1845"))
    )
    (comp (ref "Q18")
      (value "KSA992")
      (footprint "eagle-import:TRANSISTOR_TO92-ECB_P")
      (libsource (lib "eagle-import") (part "BJT_PNPKSA992"))
    )
    (comp (ref "Q19")
      (value "KSA992")
      (footprint "eagle-import:TRANSISTOR_TO92-ECB_P")
      (libsource (lib "eagle-import") (part "BJT_PNPKSA992"))
    )
    (comp (ref "Q20")
      (value "KSC1845")
      (footprint "eagle-import:TRANSISTOR_TO92-ECB_N")
      (libsource (lib "eagle-import") (part "BJT_NPNKSC1845"))
    )
    (comp (ref "Q21")
      (value "KSC1845")
      (footprint "eagle-import:TRANSISTOR_TO92-ECB_N")
      (libsource (lib "eagle-import") (part "BJT_NPNKSC1845"))
    )
    (comp (ref "Q22")
      (value "KSA992")
      (footprint "eagle-import:TRANSISTOR_TO92-ECB_P")
      (libsource (lib "eagle-import") (part "BJT_PNPKSA992"))
    )
    (comp (ref "Q23")
      (value "KSC1845")
      (footprint "eagle-import:TRANSISTOR_TO92-ECB_N")
      (libsource (lib "eagle-import") (part "BJT_NPNKSC1845"))
    )
    (comp (ref "Q24")
      (value "KSA992")
      (footprint "eagle-import:TRANSISTOR_TO92-ECB_P")
      (libsource (lib "eagle-import") (part "BJT_PNPKSA992"))
    )
    (comp (ref "R3")
      (value "10K")
      (footprint "eagle-import:MINI_MELF-0204W")
      (libsource (lib "eagle-import") (part "R-EU_MELF0204W"))
    )
    (comp (ref "R4")
      (value "10K")
      (footprint "eagle-import:MINI_MELF-0204W")
      (libsource (lib "eagle-import") (part "R-EU_MELF0204W"))
    )
    (comp (ref "R5")
      (value "250")
      (footprint "eagle-import:MINI_MELF-0204W")
      (libsource (lib "eagle-import") (part "R-EU_MELF0204W"))
    )
    (comp (ref "R6")
      (value "1K")
      (footprint "eagle-import:MINI_MELF-0204W")
      (libsource (lib "eagle-import") (part "R-EU_MELF0204W"))
    )
    (comp (ref "R7")
      (value "250")
      (footprint "eagle-import:MINI_MELF-0204W")
      (fields (field (name "SPICEPREFIX") "R"))
      (libsource (lib "eagle-import") (part "R-EU_MELF0204W"))
    )
    (comp (ref "R8")
      (value "1K")
      (footprint "eagle-import:MINI_MELF-0204W")
      (libsource (lib "eagle-import") (part "R-EU_MELF0204W"))
    )
    (comp (ref "R9")
      (value "1K")
      (footprint "eagle-import:MINI_MELF-0204W")
      (libsource (lib "eagle-import") (part "R-EU_MELF0204W"))
    )
    (comp (ref "R10")
      (value "1K")
      (footprint "eagle-import:MINI_MELF-0204W")
      (libsource (lib "eagle-import") (part "R-EU_MELF0204W"))
    )
    (comp (ref "R11")
      (value "2k")
      (footprint "eagle-import:MINI_MELF-0204W")
      (libsource (lib "eagle-import") (part "R-EU_MELF0204W"))
    )
    (comp (ref "R12")
      (value "250")
      (footprint "eagle-import:MINI_MELF-0204W")
      (libsource (lib "eagle-import") (part "R-EU_MELF0204W"))
    )
    (comp (ref "R13")
      (value "250")
      (footprint "eagle-import:MINI_MELF-0204W")
      (libsource (lib "eagle-import") (part "R-EU_MELF0204W"))
    )
    (comp (ref "R14")
      (value "10K")
      (footprint "eagle-import:MINI_MELF-0204W")
      (libsource (lib "eagle-import") (part "R-EU_MELF0204W"))
    )
    (comp (ref "R15")
      (value "10K")
      (footprint "eagle-import:MINI_MELF-0204W")
      (libsource (lib "eagle-import") (part "R-EU_MELF0204W"))
    )
    (comp (ref "R16")
      (value "10K")
      (footprint "eagle-import:MINI_MELF-0204W")
      (libsource (lib "eagle-import") (part "R-EU_MELF0204W"))
    )
    (comp (ref "R17")
      (value "10K")
      (footprint "eagle-import:MINI_MELF-0204W")
      (libsource (lib "eagle-import") (part "R-EU_MELF0204W"))
    )
    (comp (ref "R18")
      (value "250")
      (footprint "eagle-import:MINI_MELF-0204W")
      (libsource (lib "eagle-import") (part "R-EU_MELF0204W"))
    )
    (comp (ref "R19")
      (value "250")
      (footprint "eagle-import:MINI_MELF-0204W")
      (libsource (lib "eagle-import") (part "R-EU_MELF0204W"))
    )
    (comp (ref "R20")
      (value "2k")
      (footprint "eagle-import:MINI_MELF-0204W")
      (libsource (lib "eagle-import") (part "R-EU_MELF0204W"))
    )
    (comp (ref "R21")
      (value "10K")
      (footprint "eagle-import:MINI_MELF-0204W")
      (libsource (lib "eagle-import") (part "R-EU_MELF0204W"))
    )
    (comp (ref "R22")
      (value "20K")
      (footprint "eagle-import:MINI_MELF-0204W")
      (libsource (lib "eagle-import") (part "R-EU_MELF0204W"))
    )
    (comp (ref "R23")
      (value "250")
      (footprint "eagle-import:MINI_MELF-0204W")
      (libsource (lib "eagle-import") (part "R-EU_MELF0204W"))
    )
    (comp (ref "R24")
      (value "10")
      (footprint "eagle-import:MINI_MELF-0204W")
      (libsource (lib "eagle-import") (part "R-EU_MELF0204W"))
    )
    (comp (ref "R25")
      (value "10")
      (footprint "eagle-import:MINI_MELF-0204W")
      (libsource (lib "eagle-import") (part "R-EU_MELF0204W"))
    )
    (comp (ref "R26")
      (value "250")
      (footprint "eagle-import:MINI_MELF-0204W")
      (libsource (lib "eagle-import") (part "R-EU_MELF0204W"))
    )
    (comp (ref "R27")
      (value "300")
      (footprint "eagle-import:MINI_MELF-0204W")
      (libsource (lib "eagle-import") (part "R-EU_MELF0204W"))
    )
    (comp (ref "R28")
      (value "300")
      (footprint "eagle-import:MINI_MELF-0204W")
      (libsource (lib "eagle-import") (part "R-EU_MELF0204W"))
    )
    (comp (ref "R29")
      (value "10K")
      (footprint "eagle-import:MINI_MELF-0204W")
      (libsource (lib "eagle-import") (part "R-EU_MELF0204W"))
    )
    (comp (ref "R30")
      (value "10")
      (footprint "eagle-import:MINI_MELF-0204W")
      (libsource (lib "eagle-import") (part "R-EU_MELF0204W"))
    )
    (comp (ref "R31")
      (value "10")
      (footprint "eagle-import:MINI_MELF-0204W")
      (libsource (lib "eagle-import") (part "R-EU_MELF0204W"))
    )
    (comp (ref "R32")
      (value "300")
      (footprint "eagle-import:MINI_MELF-0204W")
      (libsource (lib "eagle-import") (part "R-EU_MELF0204W"))
    )
    (comp (ref "R33")
      (value "300")
      (footprint "eagle-import:MINI_MELF-0204W")
      (libsource (lib "eagle-import") (part "R-EU_MELF0204W"))
    )
    (comp (ref "R34")
      (value "10")
      (footprint "eagle-import:MINI_MELF-0204W")
      (libsource (lib "eagle-import") (part "R-EU_MELF0204W"))
    )
    (comp (ref "R35")
      (value "10")
      (footprint "eagle-import:MINI_MELF-0204W")
      (libsource (lib "eagle-import") (part "R-EU_MELF0204W"))
    )
    (comp (ref "R36")
      (value "10K")
      (footprint "eagle-import:MINI_MELF-0204W")
      (libsource (lib "eagle-import") (part "R-EU_MELF0204W"))
    )
    (comp (ref "R37")
      (value "20K")
      (footprint "eagle-import:MINI_MELF-0204W")
      (libsource (lib "eagle-import") (part "R-EU_MELF0204W"))
    )
    (comp (ref "R38")
      (value "250")
      (footprint "eagle-import:MINI_MELF-0204W")
      (libsource (lib "eagle-import") (part "R-EU_MELF0204W"))
    )
    (comp (ref "R39")
      (value "10")
      (footprint "eagle-import:MINI_MELF-0204W")
      (libsource (lib "eagle-import") (part "R-EU_MELF0204W"))
    )
    (comp (ref "R40")
      (value "10")
      (footprint "eagle-import:MINI_MELF-0204W")
      (libsource (lib "eagle-import") (part "R-EU_MELF0204W"))
    )
    (comp (ref "R41")
      (value "250")
      (footprint "eagle-import:MINI_MELF-0204W")
      (libsource (lib "eagle-import") (part "R-EU_MELF0204W"))
    )
    (comp (ref "R42")
      (value "300")
      (footprint "eagle-import:MINI_MELF-0204W")
      (libsource (lib "eagle-import") (part "R-EU_MELF0204W"))
    )
    (comp (ref "R43")
      (value "300")
      (footprint "eagle-import:MINI_MELF-0204W")
      (libsource (lib "eagle-import") (part "R-EU_MELF0204W"))
    )
    (comp (ref "R44")
      (value "10K")
      (footprint "eagle-import:MINI_MELF-0204W")
      (libsource (lib "eagle-import") (part "R-EU_MELF0204W"))
    )
    (comp (ref "R45")
      (value "10")
      (footprint "eagle-import:MINI_MELF-0204W")
      (libsource (lib "eagle-import") (part "R-EU_MELF0204W"))
    )
    (comp (ref "R46")
      (value "10")
      (footprint "eagle-import:MINI_MELF-0204W")
      (libsource (lib "eagle-import") (part "R-EU_MELF0204W"))
    )
    (comp (ref "R47")
      (value "300")
      (footprint "eagle-import:MINI_MELF-0204W")
      (libsource (lib "eagle-import") (part "R-EU_MELF0204W"))
    )
    (comp (ref "R48")
      (value "300")
      (footprint "eagle-import:MINI_MELF-0204W")
      (libsource (lib "eagle-import") (part "R-EU_MELF0204W"))
    )
    (comp (ref "R49")
      (value "10")
      (footprint "eagle-import:MINI_MELF-0204W")
      (libsource (lib "eagle-import") (part "R-EU_MELF0204W"))
    )
    (comp (ref "R50")
      (value "10")
      (footprint "eagle-import:MINI_MELF-0204W")
      (libsource (lib "eagle-import") (part "R-EU_MELF0204W"))
    )
    (comp (ref "R134")
      (value "10K")
      (footprint "eagle-import:MINI_MELF-0204W")
      (libsource (lib "eagle-import") (part "R-EU_MELF0204W"))
    )
    (comp (ref "R135")
      (value "10K")
      (footprint "eagle-import:MINI_MELF-0204W")
      (libsource (lib "eagle-import") (part "R-EU_MELF0204W"))
    )
    (comp (ref "S1")
      (value "VWV")
      (footprint "eagle-import:VWV")
      (libsource (lib "eagle-import") (part "VWV"))
    )
    (comp (ref "X1")
      (value "KK-156-3")
      (footprint "eagle-import:KK-156-3")
      (fields (field (name "MF") "MOLEX"))
      (libsource (lib "eagle-import") (part "KK-156-3"))
    )
  )
  (nets
    (net (code "1") (name "+18V") (class "Default")
      (node (ref "C14") (pin "2") (pinfunction "2_2") (pintype "passive"))
      (node (ref "C23") (pin "1") (pinfunction "1_1") (pintype "passive"))
      (node (ref "C3") (pin "2") (pinfunction "2_2") (pintype "passive"))
      (node (ref "C33") (pin "1") (pinfunction "1_1") (pintype "passive"))
      (node (ref "C69") (pin "1") (pinfunction "1_1") (pintype "passive"))
      (node (ref "C71") (pin "1") (pinfunction "1_1") (pintype "passive"))
      (node (ref "IC1") (pin "7") (pinfunction "V+_7") (pintype "power_in"))
      (node (ref "IC2") (pin "7") (pinfunction "V+_7") (pintype "power_in"))
      (node (ref "IC3") (pin "7") (pinfunction "V+_7") (pintype "power_in"))
      (node (ref "IC4") (pin "7") (pinfunction "V+_7") (pintype "power_in"))
      (node (ref "R136") (pin "2") (pinfunction "2_2") (pintype "passive"))
      (node (ref "R141") (pin "1") (pinfunction "1_1") (pintype "passive"))
      (node (ref "U$5") (pin "10") (pinfunction "O+_10") (pintype "bidirectional"))
    )
    (net (code "2") (name "-18V") (class "Default")
      (node (ref "C15") (pin "1") (pinfunction "1_1") (pintype "passive"))
      (node (ref "C24") (pin "2") (pinfunction "2_2") (pintype "passive"))
      (node (ref "C34") (pin "2") (pinfunction "2_2") (pintype "passive"))
      (node (ref "C4") (pin "1") (pinfunction "1_1") (pintype "passive"))
      (node (ref "C70") (pin "2") (pinfunction "2_2") (pintype "passive"))
      (node (ref "C72") (pin "2") (pinfunction "2_2") (pintype "passive"))
      (node (ref "IC1") (pin "4") (pinfunction "V-_4") (pintype "power_in"))
      (node (ref "IC2") (pin "4") (pinfunction "V-_4") (pintype "power_in"))
      (node (ref "IC3") (pin "4") (pinfunction "V-_4") (pintype "power_in"))
      (node (ref "IC4") (pin "4") (pinfunction "V-_4") (pintype "power_in"))
      (node (ref "R139") (pin "1") (pinfunction "1_1") (pintype "passive"))
      (node (ref "R140") (pin "1") (pinfunction "1_1") (pintype "passive"))
      (node (ref "U$5") (pin "6") (pinfunction "O-_6") (pintype "bidirectional"))
    )
    (net (code "3") (name "BOUT+") (class "Default")
      (node (ref "R29") (pin "1") (pinfunction "1_1") (pintype "passive"))
      (node (ref "R30") (pin "1") (pinfunction "1_1") (pintype "passive"))
      (node (ref "R31") (pin "2") (pinfunction "2_2") (pintype "passive"))
      (node (ref "R34") (pin "1") (pinfunction "1_1") (pintype "passive"))
      (node (ref "R35") (pin "2") (pinfunction "2_2") (pintype "passive"))
      (node (ref "R51") (pin "2") (pinfunction "2_2") (pintype "passive"))
    )
    (net (code "4") (name "BOUT-") (class "Default")
      (node (ref "R44") (pin "1") (pinfunction "1_1") (pintype "passive"))
      (node (ref "R45") (pin "1") (pinfunction "1_1") (pintype "passive"))
      (node (ref "R46") (pin "2") (pinfunction "2_2") (pintype "passive"))
      (node (ref "R49") (pin "1") (pinfunction "1_1") (pintype "passive"))
      (node (ref "R50") (pin "2") (pinfunction "2_2") (pintype "passive"))
      (node (ref "R83") (pin "2") (pinfunction "2_2") (pintype "passive"))
    )
    (net (code "5") (name "GND") (class "Default")
      (node (ref "C10") (pin "1") (pinfunction "1_1") (pintype "passive"))
      (node (ref "C11") (pin "2") (pinfunction "2_2") (pintype "passive"))
      (node (ref "C12") (pin "1") (pinfunction "1_1") (pintype "passive"))
      (node (ref "C14") (pin "1") (pinfunction "1_1") (pintype "passive"))
      (node (ref "C15") (pin "2") (pinfunction "2_2") (pintype "passive"))
      (node (ref "C17") (pin "2") (pinfunction "2_2") (pintype "passive"))
      (node (ref "C19") (pin "1") (pinfunction "1_1") (pintype "passive"))
      (node (ref "C2") (pin "2") (pinfunction "2_2") (pintype "passive"))
      (node (ref "C20") (pin "2") (pinfunction "2_2") (pintype "passive"))
      (node (ref "C22") (pin "1") (pinfunction "1_1") (pintype "passive"))
      (node (ref "C23") (pin "2") (pinfunction "2_2") (pintype "passive"))
      (node (ref "C24") (pin "1") (pinfunction "1_1") (pintype "passive"))
      (node (ref "C25") (pin "-") (pinfunction "-_-") (pintype "passive"))
      (node (ref "C26") (pin "+") (pinfunction "+_+") (pintype "passive"))
      (node (ref "C27") (pin "2") (pinfunction "2_2") (pintype "passive"))
      (node (ref "C29") (pin "1") (pinfunction "1_1") (pintype "passive"))
      (node (ref "C3") (pin "1") (pinfunction "1_1") (pintype "passive"))
      (node (ref "C30") (pin "2") (pinfunction "2_2") (pintype "passive"))
      (node (ref "C32") (pin "1") (pinfunction "1_1") (pintype "passive"))
      (node (ref "C33") (pin "2") (pinfunction "2_2") (pintype "passive"))
      (node (ref "C34") (pin "1") (pinfunction "1_1") (pintype "passive"))
      (node (ref "C35") (pin "-") (pinfunction "-_-") (pintype "passive"))
      (node (ref "C36") (pin "+") (pinfunction "+_+") (pintype "passive"))
      (node (ref "C4") (pin "2") (pinfunction "2_2") (pintype "passive"))
      (node (ref "C5") (pin "-") (pinfunction "-_-") (pintype "passive"))
      (node (ref "C6") (pin "+") (pinfunction "+_+") (pintype "passive"))
      (node (ref "C65") (pin "2") (pinfunction "2_2") (pintype "passive"))
      (node (ref "C66") (pin "2") (pinfunction "2_2") (pintype "passive"))
      (node (ref "C67") (pin "2") (pinfunction "2_2") (pintype "passive"))
      (node (ref "C68") (pin "2") (pinfunction "2_2") (pintype "passive"))
      (node (ref "C69") (pin "2") (pinfunction "2_2") (pintype "passive"))
      (node (ref "C7") (pin "-") (pinfunction "-_-") (pintype "passive"))
      (node (ref "C70") (pin "1") (pinfunction "1_1") (pintype "passive"))
      (node (ref "C74") (pin "2") (pinfunction "2_2") (pintype "passive"))
      (node (ref "C75") (pin "1") (pinfunction "1_1") (pintype "passive"))
      (node (ref "C8") (pin "+") (pinfunction "+_+") (pintype "passive"))
      (node (ref "C9") (pin "2") (pinfunction "2_2") (pintype "passive"))
      (node (ref "IC1") (pin "3") (pinfunction "+IN_3") (pintype "input"))
      (node (ref "IC2") (pin "3") (pinfunction "+IN_3") (pintype "input"))
      (node (ref "LED17") (pin "C") (pinfunction "C_C") (pintype "passive"))
      (node (ref "LED18") (pin "A") (pinfunction "A_A") (pintype "passive"))
      (node (ref "PAD3") (pin "P$1") (pinfunction "P$1_P$1") (pintype "bidirectional"))
      (node (ref "PAD4") (pin "P$1") (pinfunction "P$1_P$1") (pintype "bidirectional"))
      (node (ref "R107") (pin "2") (pinfunction "2_2") (pintype "passive"))
      (node (ref "R108") (pin "1") (pinfunction "1_1") (pintype "passive"))
      (node (ref "R11") (pin "1") (pinfunction "1_1") (pintype "passive"))
      (node (ref "R111") (pin "1") (pinfunction "1_1") (pintype "passive"))
      (node (ref "R134") (pin "1") (pinfunction "1_1") (pintype "passive"))
      (node (ref "R135") (pin "1") (pinfunction "1_1") (pintype "passive"))
      (node (ref "R137") (pin "1") (pinfunction "1_1") (pintype "passive"))
      (node (ref "R15") (pin "1") (pinfunction "1_1") (pintype "passive"))
      (node (ref "R16") (pin "2") (pinfunction "2_2") (pintype "passive"))
      (node (ref "R20") (pin "1") (pinfunction "1_1") (pintype "passive"))
      (node (ref "R3") (pin "1") (pinfunction "1_1") (pintype "passive"))
      (node (ref "R4") (pin "2") (pinfunction "2_2") (pintype "passive"))
      (node (ref "R52") (pin "1") (pinfunction "1_1") (pintype "passive"))
      (node (ref "R63") (pin "1") (pinfunction "1_1") (pintype "passive"))
      (node (ref "R75") (pin "2") (pinfunction "2_2") (pintype "passive"))
      (node (ref "R76") (pin "1") (pinfunction "1_1") (pintype "passive"))
      (node (ref "R79") (pin "1") (pinfunction "1_1") (pintype "passive"))
      (node (ref "R84") (pin "1") (pinfunction "1_1") (pintype "passive"))
      (node (ref "R95") (pin "1") (pinfunction "1_1") (pintype "passive"))
      (node (ref "U$5") (pin "11") (pinfunction "GND_11") (pintype "bidirectional"))
      (node (ref "U$5") (pin "12") (pinfunction "GND_12") (pintype "bidirectional"))
      (node (ref "U$5") (pin "13") (pinfunction "GND_13") (pintype "bidirectional"))
      (node (ref "U$5") (pin "14") (pinfunction "GND_14") (pintype "bidirectional"))
      (node (ref "U$5") (pin "15") (pinfunction "GND_15") (pintype "bidirectional"))
      (node (ref "U$5") (pin "4") (pinfunction "GND_4") (pintype "bidirectional"))
      (node (ref "X1") (pin "2") (pinfunction "S_2") (pintype "passive"))
    )
    (net (code "6") (name "IN+") (class "Default")
      (node (ref "Q1") (pin "4") (pinfunction "G_4") (pintype "passive"))
      (node (ref "Q4") (pin "4") (pinfunction "G_4") (pintype "passive"))
      (node (ref "R134") (pin "2") (pinfunction "2_2") (pintype "passive"))
      (node (ref "X1") (pin "3") (pinfunction "S_3") (pintype "passive"))
    )
    (net (code "7") (name "IN-") (class "Default")
      (node (ref "Q1") (pin "1") (pinfunction "G_1") (pintype "passive"))
      (node (ref "Q4") (pin "1") (pinfunction "G_1") (pintype "passive"))
      (node (ref "R135") (pin "2") (pinfunction "2_2") (pintype "passive"))
      (node (ref "X1") (pin "1") (pinfunction "S_1") (pintype "passive"))
    )
    (net (code "8") (name "Net-(C1-Pad2)") (class "Default")
      (node (ref "C1") (pin "2") (pinfunction "2_2") (pintype "passive"))
      (node (ref "R133") (pin "1") (pinfunction "1_1") (pintype "passive"))
    )
    (net (code "9") (name "Net-(C17-Pad1)") (class "Default")
      (node (ref "C17") (pin "1") (pinfunction "1_1") (pintype "passive"))
      (node (ref "Q26") (pin "B") (pinfunction "B_B") (pintype "passive"))
      (node (ref "Q27") (pin "B") (pinfunction "B_B") (pintype "passive"))
      (node (ref "R51") (pin "1") (pinfunction "1_1") (pintype "passive"))
      (node (ref "R52") (pin "2") (pinfunction "2_2") (pintype "passive"))
    )
    (net (code "10") (name "Net-(C18-Pad1)") (class "Default")
      (node (ref "C18") (pin "1") (pinfunction "1_1") (pintype "passive"))
      (node (ref "C19") (pin "2") (pinfunction "2_2") (pintype "passive"))
      (node (ref "Q39") (pin "C") (pinfunction "C_C") (pintype "passive"))
      (node (ref "Q43") (pin "C") (pinfunction "C_C") (pintype "passive"))
      (node (ref "Q45") (pin "C") (pinfunction "C_C") (pintype "passive"))
      (node (ref "Q46") (pin "B") (pinfunction "B_B") (pintype "passive"))
      (node (ref "R73") (pin "2") (pinfunction "2_2") (pintype "passive"))
      (node (ref "R75") (pin "1") (pinfunction "1_1") (pintype "passive"))
    )
    (net (code "11") (name "Net-(C27-Pad1)") (class "Default")
      (node (ref "C27") (pin "1") (pinfunction "1_1") (pintype "passive"))
      (node (ref "Q53") (pin "B") (pinfunction "B_B") (pintype "passive"))
      (node (ref "Q54") (pin "B") (pinfunction "B_B") (pintype "passive"))
      (node (ref "R83") (pin "1") (pinfunction "1_1") (pintype "passive"))
      (node (ref "R84") (pin "2") (pinfunction "2_2") (pintype "passive"))
    )
    (net (code "12") (name "Net-(C28-Pad1)") (class "Default")
      (node (ref "C28") (pin "1") (pinfunction "1_1") (pintype "passive"))
      (node (ref "C29") (pin "2") (pinfunction "2_2") (pintype "passive"))
      (node (ref "Q66") (pin "C") (pinfunction "C_C") (pintype "passive"))
      (node (ref "Q70") (pin "C") (pinfunction "C_C") (pintype "passive"))
      (node (ref "Q72") (pin "C") (pinfunction "C_C") (pintype "passive"))
      (node (ref "Q73") (pin "B") (pinfunction "B_B") (pintype "passive"))
      (node (ref "R105") (pin "2") (pinfunction "2_2") (pintype "passive"))
      (node (ref "R107") (pin "1") (pinfunction "1_1") (pintype "passive"))
    )
    (net (code "13") (name "Net-(D1-PadC)") (class "Default")
      (node (ref "D1") (pin "C") (pinfunction "C_C") (pintype "passive"))
      (node (ref "D2") (pin "A") (pinfunction "A_A") (pintype "passive"))
    )
    (net (code "14") (name "Net-(D2-PadC)") (class "Default")
      (node (ref "D2") (pin "C") (pinfunction "C_C") (pintype "passive"))
      (node (ref "Q25") (pin "B") (pinfunction "B_B") (pintype "passive"))
      (node (ref "R53") (pin "2") (pinfunction "2_2") (pintype "passive"))
    )
    (net (code "15") (name "Net-(D3-PadA)") (class "Default")
      (node (ref "D3") (pin "A") (pinfunction "A_A") (pintype "passive"))
      (node (ref "Q28") (pin "B") (pinfunction "B_B") (pintype "passive"))
      (node (ref "R53") (pin "1") (pinfunction "1_1") (pintype "passive"))
    )
    (net (code "16") (name "Net-(D3-PadC)") (class "Default")
      (node (ref "D3") (pin "C") (pinfunction "C_C") (pintype "passive"))
      (node (ref "D4") (pin "A") (pinfunction "A_A") (pintype "passive"))
    )
    (net (code "17") (name "Net-(D5-PadA)") (class "Default")
      (node (ref "D5") (pin "A") (pinfunction "A_A") (pintype "passive"))
      (node (ref "Q25") (pin "C") (pinfunction "C_C") (pintype "passive"))
      (node (ref "Q29") (pin "B") (pinfunction "B_B") (pintype "passive"))
    )
    (net (code "18") (name "Net-(D5-PadC)") (class "Default")
      (node (ref "D5") (pin "C") (pinfunction "C_C") (pintype "passive"))
      (node (ref "Q30") (pin "B") (pinfunction "B_B") (pintype "passive"))
      (node (ref "R55") (pin "2") (pinfunction "2_2") (pintype "passive"))
    )
    (net (code "19") (name "Net-(D6-PadA)") (class "Default")
      (node (ref "D6") (pin "A") (pinfunction "A_A") (pintype "passive"))
      (node (ref "Q31") (pin "B") (pinfunction "B_B") (pintype "passive"))
      (node (ref "R56") (pin "1") (pinfunction "1_1") (pintype "passive"))
    )
    (net (code "20") (name "Net-(D6-PadC)") (class "Default")
      (node (ref "D6") (pin "C") (pinfunction "C_C") (pintype "passive"))
      (node (ref "Q28") (pin "C") (pinfunction "C_C") (pintype "passive"))
      (node (ref "Q32") (pin "B") (pinfunction "B_B") (pintype "passive"))
    )
    (net (code "21") (name "Net-(D7-PadC)") (class "Default")
      (node (ref "D7") (pin "C") (pinfunction "C_C") (pintype "passive"))
      (node (ref "D8") (pin "A") (pinfunction "A_A") (pintype "passive"))
    )
    (net (code "22") (name "Net-(D8-PadC)") (class "Default")
      (node (ref "D8") (pin "C") (pinfunction "C_C") (pintype "passive"))
      (node (ref "Q52") (pin "B") (pinfunction "B_B") (pintype "passive"))
      (node (ref "R85") (pin "2") (pinfunction "2_2") (pintype "passive"))
    )
    (net (code "23") (name "Net-(D9-PadA)") (class "Default")
      (node (ref "D9") (pin "A") (pinfunction "A_A") (pintype "passive"))
      (node (ref "Q55") (pin "B") (pinfunction "B_B") (pintype "passive"))
      (node (ref "R85") (pin "1") (pinfunction "1_1") (pintype "passive"))
    )
    (net (code "24") (name "Net-(D10-PadA)") (class "Default")
      (node (ref "D10") (pin "A") (pinfunction "A_A") (pintype "passive"))
      (node (ref "D9") (pin "C") (pinfunction "C_C") (pintype "passive"))
    )
    (net (code "25") (name "Net-(D11-PadA)") (class "Default")
      (node (ref "D11") (pin "A") (pinfunction "A_A") (pintype "passive"))
      (node (ref "Q52") (pin "C") (pinfunction "C_C") (pintype "passive"))
      (node (ref "Q56") (pin "B") (pinfunction "B_B") (pintype "passive"))
    )
    (net (code "26") (name "Net-(D11-PadC)") (class "Default")
      (node (ref "D11") (pin "C") (pinfunction "C_C") (pintype "passive"))
      (node (ref "Q57") (pin "B") (pinfunction "B_B") (pintype "passive"))
      (node (ref "R87") (pin "2") (pinfunction "2_2") (pintype "passive"))
    )
    (net (code "27") (name "Net-(D12-PadA)") (class "Default")
      (node (ref "D12") (pin "A") (pinfunction "A_A") (pintype "passive"))
      (node (ref "Q58") (pin "B") (pinfunction "B_B") (pintype "passive"))
      (node (ref "R88") (pin "1") (pinfunction "1_1") (pintype "passive"))
    )
    (net (code "28") (name "Net-(D12-PadC)") (class "Default")
      (node (ref "D12") (pin "C") (pinfunction "C_C") (pintype "passive"))
      (node (ref "Q55") (pin "C") (pinfunction "C_C") (pintype "passive"))
      (node (ref "Q59") (pin "B") (pinfunction "B_B") (pintype "passive"))
    )
    (net (code "29") (name "Net-(IC1--IN)") (class "Default")
      (node (ref "C13") (pin "2") (pinfunction "2_2") (pintype "passive"))
      (node (ref "IC1") (pin "2") (pinfunction "-IN_2") (pintype "input"))
      (node (ref "R29") (pin "2") (pinfunction "2_2") (pintype "passive"))
    )
    (net (code "30") (name "Net-(IC1-CMP2)") (class "Default")
      (node (ref "C13") (pin "1") (pinfunction "1_1") (pintype "passive"))
      (node (ref "IC1") (pin "6") (pinfunction "OUT_6") (pintype "output"))
      (node (ref "IC1") (pin "8") (pinfunction "CMP2_8") (pintype "passive"))
      (node (ref "R21") (pin "1") (pinfunction "1_1") (pintype "passive"))
    )
    (net (code "31") (name "Net-(IC2--IN)") (class "Default")
      (node (ref "C16") (pin "2") (pinfunction "2_2") (pintype "passive"))
      (node (ref "IC2") (pin "2") (pinfunction "-IN_2") (pintype "input"))
      (node (ref "R44") (pin "2") (pinfunction "2_2") (pintype "passive"))
    )
    (net (code "32") (name "Net-(IC2-CMP2)") (class "Default")
      (node (ref "C16") (pin "1") (pinfunction "1_1") (pintype "passive"))
      (node (ref "IC2") (pin "6") (pinfunction "OUT_6") (pintype "output"))
      (node (ref "IC2") (pin "8") (pinfunction "CMP2_8") (pintype "passive"))
      (node (ref "R36") (pin "1") (pinfunction "1_1") (pintype "passive"))
    )
    (net (code "33") (name "Net-(IC3-+IN)") (class "Default")
      (node (ref "C22") (pin "2") (pinfunction "2_2") (pintype "passive"))
      (node (ref "IC3") (pin "3") (pinfunction "+IN_3") (pintype "input"))
      (node (ref "R82") (pin "2") (pinfunction "2_2") (pintype "passive"))
    )
    (net (code "34") (name "Net-(IC3--IN)") (class "Default")
      (node (ref "C21") (pin "2") (pinfunction "2_2") (pintype "passive"))
      (node (ref "IC3") (pin "2") (pinfunction "-IN_2") (pintype "input"))
      (node (ref "R79") (pin "2") (pinfunction "2_2") (pintype "passive"))
    )
    (net (code "35") (name "Net-(IC3-OUT)") (class "Default")
      (node (ref "C21") (pin "1") (pinfunction "1_1") (pintype "passive"))
      (node (ref "IC3") (pin "6") (pinfunction "OUT_6") (pintype "output"))
      (node (ref "R68") (pin "1") (pinfunction "1_1") (pintype "passive"))
      (node (ref "R69") (pin "2") (pinfunction "2_2") (pintype "passive"))
    )
    (net (code "36") (name "Net-(IC4-+IN)") (class "Default")
      (node (ref "C32") (pin "2") (pinfunction "2_2") (pintype "passive"))
      (node (ref "IC4") (pin "3") (pinfunction "+IN_3") (pintype "input"))
      (node (ref "R114") (pin "2") (pinfunction "2_2") (pintype "passive"))
    )
    (net (code "37") (name "Net-(IC4--IN)") (class "Default")
      (node (ref "C31") (pin "2") (pinfunction "2_2") (pintype "passive"))
      (node (ref "IC4") (pin "2") (pinfunction "-IN_2") (pintype "input"))
      (node (ref "R111") (pin "2") (pinfunction "2_2") (pintype "passive"))
    )
    (net (code "38") (name "Net-(IC4-OUT)") (class "Default")
      (node (ref "C31") (pin "1") (pinfunction "1_1") (pintype "passive"))
      (node (ref "IC4") (pin "6") (pinfunction "OUT_6") (pintype "output"))
      (node (ref "R100") (pin "1") (pinfunction "1_1") (pintype "passive"))
      (node (ref "R101") (pin "2") (pinfunction "2_2") (pintype "passive"))
    )
    (net (code "39") (name "Net-(LED1-PadC)") (class "Default")
      (node (ref "LED1") (pin "C") (pinfunction "C_C") (pintype "passive"))
      (node (ref "Q2") (pin "B") (pinfunction "B_B") (pintype "passive"))
      (node (ref "R3") (pin "2") (pinfunction "2_2") (pintype "passive"))
    )
    (net (code "40") (name "Net-(LED2-PadA)") (class "Default")
      (node (ref "LED2") (pin "A") (pinfunction "A_A") (pintype "passive"))
      (node (ref "Q3") (pin "B") (pinfunction "B_B") (pintype "passive"))
      (node (ref "R4") (pin "1") (pinfunction "1_1") (pintype "passive"))
    )
    (net (code "41") (name "Net-(LED5-PadC)") (class "Default")
      (node (ref "LED5") (pin "C") (pinfunction "C_C") (pintype "passive"))
      (node (ref "Q11") (pin "B") (pinfunction "B_B") (pintype "passive"))
      (node (ref "R22") (pin "2") (pinfunction "2_2") (pintype "passive"))
    )
    (net (code "42") (name "Net-(LED6-PadA)") (class "Default")
      (node (ref "LED6") (pin "A") (pinfunction "A_A") (pintype "passive"))
      (node (ref "Q12") (pin "B") (pinfunction "B_B") (pintype "passive"))
      (node (ref "R22") (pin "1") (pinfunction "1_1") (pintype "passive"))
    )
    (net (code "43") (name "Net-(LED7-PadC)") (class "Default")
      (node (ref "LED7") (pin "C") (pinfunction "C_C") (pintype "passive"))
      (node (ref "Q19") (pin "B") (pinfunction "B_B") (pintype "passive"))
      (node (ref "R37") (pin "2") (pinfunction "2_2") (pintype "passive"))
    )
    (net (code "44") (name "Net-(LED8-PadA)") (class "Default")
      (node (ref "LED8") (pin "A") (pinfunction "A_A") (pintype "passive"))
      (node (ref "Q20") (pin "B") (pinfunction "B_B") (pintype "passive"))
      (node (ref "R37") (pin "1") (pinfunction "1_1") (pintype "passive"))
    )
    (net (code "45") (name "Net-(LED9-PadA)") (class "Default")
      (node (ref "LED9") (pin "A") (pinfunction "A_A") (pintype "passive"))
      (node (ref "Q35") (pin "E") (pinfunction "E_E") (pintype "passive"))
      (node (ref "R62") (pin "1") (pinfunction "1_1") (pintype "passive"))
    )
    (net (code "46") (name "Net-(LED9-PadC)") (class "Default")
      (node (ref "LED9") (pin "C") (pinfunction "C_C") (pintype "passive"))
      (node (ref "Q39") (pin "B") (pinfunction "B_B") (pintype "passive"))
      (node (ref "R65") (pin "2") (pinfunction "2_2") (pintype "passive"))
    )
    (net (code "47") (name "Net-(LED10-PadA)") (class "Default")
      (node (ref "LED10") (pin "A") (pinfunction "A_A") (pintype "passive"))
      (node (ref "Q40") (pin "B") (pinfunction "B_B") (pintype "passive"))
      (node (ref "R65") (pin "1") (pinfunction "1_1") (pintype "passive"))
    )
    (net (code "48") (name "Net-(LED10-PadC)") (class "Default")
      (node (ref "LED10") (pin "C") (pinfunction "C_C") (pintype "passive"))
      (node (ref "Q38") (pin "E") (pinfunction "E_E") (pintype "passive"))
      (node (ref "R64") (pin "2") (pinfunction "2_2") (pintype "passive"))
    )
    (net (code "49") (name "Net-(LED11-PadA)") (class "Default")
      (node (ref "LED11") (pin "A") (pinfunction "A_A") (pintype "passive"))
      (node (ref "Q62") (pin "E") (pinfunction "E_E") (pintype "passive"))
      (node (ref "R94") (pin "1") (pinfunction "1_1") (pintype "passive"))
    )
    (net (code "50") (name "Net-(LED11-PadC)") (class "Default")
      (node (ref "LED11") (pin "C") (pinfunction "C_C") (pintype "passive"))
      (node (ref "Q66") (pin "B") (pinfunction "B_B") (pintype "passive"))
      (node (ref "R97") (pin "2") (pinfunction "2_2") (pintype "passive"))
    )
    (net (code "51") (name "Net-(LED12-PadA)") (class "Default")
      (node (ref "LED12") (pin "A") (pinfunction "A_A") (pintype "passive"))
      (node (ref "Q67") (pin "B") (pinfunction "B_B") (pintype "passive"))
      (node (ref "R97") (pin "1") (pinfunction "1_1") (pintype "passive"))
    )
    (net (code "52") (name "Net-(LED12-PadC)") (class "Default")
      (node (ref "LED12") (pin "C") (pinfunction "C_C") (pintype "passive"))
      (node (ref "Q65") (pin "E") (pinfunction "E_E") (pintype "passive"))
      (node (ref "R96") (pin "2") (pinfunction "2_2") (pintype "passive"))
    )
    (net (code "53") (name "Net-(LED17-PadA)") (class "Default")
      (node (ref "LED17") (pin "A") (pinfunction "A_A") (pintype "passive"))
      (node (ref "R131") (pin "1") (pinfunction "1_1") (pintype "passive"))
    )
    (net (code "54") (name "Net-(LED18-PadC)") (class "Default")
      (node (ref "LED18") (pin "C") (pinfunction "C_C") (pintype "passive"))
      (node (ref "R132") (pin "2") (pinfunction "2_2") (pintype "passive"))
    )
    (net (code "55") (name "Net-(Q1A-D)") (class "Default")
      (node (ref "Q1") (pin "2") (pinfunction "D_2") (pintype "passive"))
      (node (ref "Q6") (pin "5") (pinfunction "E_5") (pintype "passive"))
      (node (ref "Q7") (pin "6") (pinfunction "C_6") (pintype "passive"))
    )
    (net (code "56") (name "Net-(Q1A-S)") (class "Default")
      (node (ref "Q1") (pin "3") (pinfunction "S_3") (pintype "passive"))
      (node (ref "R6") (pin "1") (pinfunction "1_1") (pintype "passive"))
    )
    (net (code "57") (name "Net-(Q1B-D)") (class "Default")
      (node (ref "Q1") (pin "5") (pinfunction "D_5") (pintype "passive"))
      (node (ref "Q6") (pin "2") (pinfunction "E_2") (pintype "passive"))
      (node (ref "Q7") (pin "4") (pinfunction "C_4") (pintype "passive"))
    )
    (net (code "58") (name "Net-(Q1B-S)") (class "Default")
      (node (ref "Q1") (pin "6") (pinfunction "S_6") (pintype "passive"))
      (node (ref "R8") (pin "1") (pinfunction "1_1") (pintype "passive"))
    )
    (net (code "59") (name "Net-(Q2-PadC)") (class "Default")
      (node (ref "Q2") (pin "C") (pinfunction "C_C") (pintype "passive"))
      (node (ref "R6") (pin "2") (pinfunction "2_2") (pintype "passive"))
      (node (ref "R8") (pin "2") (pinfunction "2_2") (pintype "passive"))
    )
    (net (code "60") (name "Net-(Q2-PadE)") (class "Default")
      (node (ref "Q2") (pin "E") (pinfunction "E_E") (pintype "passive"))
      (node (ref "R5") (pin "1") (pinfunction "1_1") (pintype "passive"))
    )
    (net (code "61") (name "Net-(Q3-PadC)") (class "Default")
      (node (ref "Q3") (pin "C") (pinfunction "C_C") (pintype "passive"))
      (node (ref "R10") (pin "1") (pinfunction "1_1") (pintype "passive"))
      (node (ref "R9") (pin "1") (pinfunction "1_1") (pintype "passive"))
    )
    (net (code "62") (name "Net-(Q3-PadE)") (class "Default")
      (node (ref "Q3") (pin "E") (pinfunction "E_E") (pintype "passive"))
      (node (ref "R7") (pin "2") (pinfunction "2_2") (pintype "passive"))
    )
    (net (code "63") (name "Net-(Q4A-D)") (class "Default")
      (node (ref "Q4") (pin "2") (pinfunction "D_2") (pintype "passive"))
      (node (ref "Q5") (pin "5") (pinfunction "E_5") (pintype "passive"))
      (node (ref "Q8") (pin "4") (pinfunction "C_4") (pintype "passive"))
    )
    (net (code "64") (name "Net-(Q4A-S)") (class "Default")
      (node (ref "Q4") (pin "3") (pinfunction "S_3") (pintype "passive"))
      (node (ref "R9") (pin "2") (pinfunction "2_2") (pintype "passive"))
    )
    (net (code "65") (name "Net-(Q4B-D)") (class "Default")
      (node (ref "Q4") (pin "5") (pinfunction "D_5") (pintype "passive"))
      (node (ref "Q5") (pin "2") (pinfunction "E_2") (pintype "passive"))
      (node (ref "Q8") (pin "6") (pinfunction "C_6") (pintype "passive"))
    )
    (net (code "66") (name "Net-(Q4B-S)") (class "Default")
      (node (ref "Q4") (pin "6") (pinfunction "S_6") (pintype "passive"))
      (node (ref "R10") (pin "2") (pinfunction "2_2") (pintype "passive"))
    )
    (net (code "67") (name "Net-(Q5A-B)") (class "Default")
      (node (ref "Q5") (pin "1") (pinfunction "B_1") (pintype "passive"))
      (node (ref "Q5") (pin "3") (pinfunction "B_3") (pintype "passive"))
      (node (ref "R14") (pin "1") (pinfunction "1_1") (pintype "passive"))
      (node (ref "R15") (pin "2") (pinfunction "2_2") (pintype "passive"))
    )
    (net (code "68") (name "Net-(Q6A-B)") (class "Default")
      (node (ref "Q6") (pin "1") (pinfunction "B_1") (pintype "passive"))
      (node (ref "Q6") (pin "3") (pinfunction "B_3") (pintype "passive"))
      (node (ref "R16") (pin "1") (pinfunction "1_1") (pintype "passive"))
      (node (ref "R17") (pin "2") (pinfunction "2_2") (pintype "passive"))
    )
    (net (code "69") (name "Net-(Q7A-B)") (class "Default")
      (node (ref "LED4") (pin "A") (pinfunction "A_A") (pintype "passive"))
      (node (ref "Q7") (pin "1") (pinfunction "B_1") (pintype "passive"))
      (node (ref "Q7") (pin "3") (pinfunction "B_3") (pintype "passive"))
      (node (ref "R17") (pin "1") (pinfunction "1_1") (pintype "passive"))
    )
    (net (code "70") (name "Net-(Q7A-E)") (class "Default")
      (node (ref "Q7") (pin "5") (pinfunction "E_5") (pintype "passive"))
      (node (ref "R13") (pin "2") (pinfunction "2_2") (pintype "passive"))
    )
    (net (code "71") (name "Net-(Q7B-E)") (class "Default")
      (node (ref "Q7") (pin "2") (pinfunction "E_2") (pintype "passive"))
      (node (ref "R19") (pin "2") (pinfunction "2_2") (pintype "passive"))
    )
    (net (code "72") (name "Net-(Q8A-B)") (class "Default")
      (node (ref "LED3") (pin "C") (pinfunction "C_C") (pintype "passive"))
      (node (ref "Q8") (pin "1") (pinfunction "B_1") (pintype "passive"))
      (node (ref "Q8") (pin "3") (pinfunction "B_3") (pintype "passive"))
      (node (ref "R14") (pin "2") (pinfunction "2_2") (pintype "passive"))
    )
    (net (code "73") (name "Net-(Q8A-E)") (class "Default")
      (node (ref "Q8") (pin "5") (pinfunction "E_5") (pintype "passive"))
      (node (ref "R18") (pin "1") (pinfunction "1_1") (pintype "passive"))
    )
    (net (code "74") (name "Net-(Q8B-E)") (class "Default")
      (node (ref "Q8") (pin "2") (pinfunction "E_2") (pintype "passive"))
      (node (ref "R12") (pin "1") (pinfunction "1_1") (pintype "passive"))
    )
    (net (code "75") (name "Net-(Q9-PadE)") (class "Default")
      (node (ref "Q9") (pin "E") (pinfunction "E_E") (pintype "passive"))
      (node (ref "R25") (pin "1") (pinfunction "1_1") (pintype "passive"))
    )
    (net (code "76") (name "Net-(Q10-PadE)") (class "Default")
      (node (ref "Q10") (pin "E") (pinfunction "E_E") (pintype "passive"))
      (node (ref "R24") (pin "2") (pinfunction "2_2") (pintype "passive"))
    )
    (net (code "77") (name "Net-(Q11-PadC)") (class "Default")
      (node (ref "Q11") (pin "C") (pinfunction "C_C") (pintype "passive"))
      (node (ref "R24") (pin "1") (pinfunction "1_1") (pintype "passive"))
      (node (ref "R27") (pin "2") (pinfunction "2_2") (pintype "passive"))
      (node (ref "R32") (pin "2") (pinfunction "2_2") (pintype "passive"))
    )
    (net (code "78") (name "Net-(Q11-PadE)") (class "Default")
      (node (ref "Q11") (pin "E") (pinfunction "E_E") (pintype "passive"))
      (node (ref "R23") (pin "1") (pinfunction "1_1") (pintype "passive"))
    )
    (net (code "79") (name "Net-(Q12-PadC)") (class "Default")
      (node (ref "Q12") (pin "C") (pinfunction "C_C") (pintype "passive"))
      (node (ref "R25") (pin "2") (pinfunction "2_2") (pintype "passive"))
      (node (ref "R28") (pin "1") (pinfunction "1_1") (pintype "passive"))
      (node (ref "R33") (pin "1") (pinfunction "1_1") (pintype "passive"))
    )
    (net (code "80") (name "Net-(Q12-PadE)") (class "Default")
      (node (ref "Q12") (pin "E") (pinfunction "E_E") (pintype "passive"))
      (node (ref "R26") (pin "2") (pinfunction "2_2") (pintype "passive"))
    )
    (net (code "81") (name "Net-(Q13-PadB)") (class "Default")
      (node (ref "Q13") (pin "B") (pinfunction "B_B") (pintype "passive"))
      (node (ref "R27") (pin "1") (pinfunction "1_1") (pintype "passive"))
    )
    (net (code "82") (name "Net-(Q13-PadE)") (class "Default")
      (node (ref "Q13") (pin "E") (pinfunction "E_E") (pintype "passive"))
      (node (ref "R30") (pin "2") (pinfunction "2_2") (pintype "passive"))
    )
    (net (code "83") (name "Net-(Q14-PadB)") (class "Default")
      (node (ref "Q14") (pin "B") (pinfunction "B_B") (pintype "passive"))
      (node (ref "R28") (pin "2") (pinfunction "2_2") (pintype "passive"))
    )
    (net (code "84") (name "Net-(Q14-PadE)") (class "Default")
      (node (ref "Q14") (pin "E") (pinfunction "E_E") (pintype "passive"))
      (node (ref "R31") (pin "1") (pinfunction "1_1") (pintype "passive"))
    )
    (net (code "85") (name "Net-(Q15-PadB)") (class "Default")
      (node (ref "Q15") (pin "B") (pinfunction "B_B") (pintype "passive"))
      (node (ref "R32") (pin "1") (pinfunction "1_1") (pintype "passive"))
    )
    (net (code "86") (name "Net-(Q15-PadE)") (class "Default")
      (node (ref "Q15") (pin "E") (pinfunction "E_E") (pintype "passive"))
      (node (ref "R34") (pin "2") (pinfunction "2_2") (pintype "passive"))
    )
    (net (code "87") (name "Net-(Q16-PadB)") (class "Default")
      (node (ref "Q16") (pin "B") (pinfunction "B_B") (pintype "passive"))
      (node (ref "R33") (pin "2") (pinfunction "2_2") (pintype "passive"))
    )
    (net (code "88") (name "Net-(Q16-PadE)") (class "Default")
      (node (ref "Q16") (pin "E") (pinfunction "E_E") (pintype "passive"))
      (node (ref "R35") (pin "1") (pinfunction "1_1") (pintype "passive"))
    )
    (net (code "89") (name "Net-(Q17-PadE)") (class "Default")
      (node (ref "Q17") (pin "E") (pinfunction "E_E") (pintype "passive"))
      (node (ref "R40") (pin "1") (pinfunction "1_1") (pintype "passive"))
    )
    (net (code "90") (name "Net-(Q18-PadE)") (class "Default")
      (node (ref "Q18") (pin "E") (pinfunction "E_E") (pintype "passive"))
      (node (ref "R39") (pin "2") (pinfunction "2_2") (pintype "passive"))
    )
    (net (code "91") (name "Net-(Q19-PadC)") (class "Default")
      (node (ref "Q19") (pin "C") (pinfunction "C_C") (pintype "passive"))
      (node (ref "R39") (pin "1") (pinfunction "1_1") (pintype "passive"))
      (node (ref "R42") (pin "2") (pinfunction "2_2") (pintype "passive"))
      (node (ref "R47") (pin "2") (pinfunction "2_2") (pintype "passive"))
    )
    (net (code "92") (name "Net-(Q19-PadE)") (class "Default")
      (node (ref "Q19") (pin "E") (pinfunction "E_E") (pintype "passive"))
      (node (ref "R38") (pin "1") (pinfunction "1_1") (pintype "passive"))
    )
    (net (code "93") (name "Net-(Q20-PadC)") (class "Default")
      (node (ref "Q20") (pin "C") (pinfunction "C_C") (pintype "passive"))
      (node (ref "R40") (pin "2") (pinfunction "2_2") (pintype "passive"))
      (node (ref "R43") (pin "1") (pinfunction "1_1") (pintype "passive"))
      (node (ref "R48") (pin "1") (pinfunction "1_1") (pintype "passive"))
    )
    (net (code "94") (name "Net-(Q20-PadE)") (class "Default")
      (node (ref "Q20") (pin "E") (pinfunction "E_E") (pintype "passive"))
      (node (ref "R41") (pin "2") (pinfunction "2_2") (pintype "passive"))
    )
    (net (code "95") (name "Net-(Q21-PadB)") (class "Default")
      (node (ref "Q21") (pin "B") (pinfunction "B_B") (pintype "passive"))
      (node (ref "R42") (pin "1") (pinfunction "1_1") (pintype "passive"))
    )
    (net (code "96") (name "Net-(Q21-PadE)") (class "Default")
      (node (ref "Q21") (pin "E") (pinfunction "E_E") (pintype "passive"))
      (node (ref "R45") (pin "2") (pinfunction "2_2") (pintype "passive"))
    )
    (net (code "97") (name "Net-(Q22-PadB)") (class "Default")
      (node (ref "Q22") (pin "B") (pinfunction "B_B") (pintype "passive"))
      (node (ref "R43") (pin "2") (pinfunction "2_2") (pintype "passive"))
    )
    (net (code "98") (name "Net-(Q22-PadE)") (class "Default")
      (node (ref "Q22") (pin "E") (pinfunction "E_E") (pintype "passive"))
      (node (ref "R46") (pin "1") (pinfunction "1_1") (pintype "passive"))
    )
    (net (code "99") (name "Net-(Q23-PadB)") (class "Default")
      (node (ref "Q23") (pin "B") (pinfunction "B_B") (pintype "passive"))
      (node (ref "R47") (pin "1") (pinfunction "1_1") (pintype "passive"))
    )
    (net (code "100") (name "Net-(Q23-PadE)") (class "Default")
      (node (ref "Q23") (pin "E") (pinfunction "E_E") (pintype "passive"))
      (node (ref "R49") (pin "2") (pinfunction "2_2") (pintype "passive"))
    )
    (net (code "101") (name "Net-(Q24-PadB)") (class "Default")
      (node (ref "Q24") (pin "B") (pinfunction "B_B") (pintype "passive"))
      (node (ref "R48") (pin "2") (pinfunction "2_2") (pintype "passive"))
    )
    (net (code "102") (name "Net-(Q24-PadE)") (class "Default")
      (node (ref "Q24") (pin "E") (pinfunction "E_E") (pintype "passive"))
      (node (ref "R50") (pin "1") (pinfunction "1_1") (pintype "passive"))
    )
    (net (code "103") (name "Net-(Q25-PadE)") (class "Default")
      (node (ref "Q25") (pin "E") (pinfunction "E_E") (pintype "passive"))
      (node (ref "R54") (pin "1") (pinfunction "1_1") (pintype "passive"))
    )
    (net (code "104") (name "Net-(Q26-PadC)") (class "Default")
      (node (ref "Q26") (pin "C") (pinfunction "C_C") (pintype "passive"))
      (node (ref "Q31") (pin "E") (pinfunction "E_E") (pintype "passive"))
      (node (ref "R60") (pin "1") (pinfunction "1_1") (pintype "passive"))
    )
    (net (code "105") (name "Net-(Q26-PadE)") (class "Default")
      (node (ref "Q26") (pin "E") (pinfunction "E_E") (pintype "passive"))
      (node (ref "R55") (pin "1") (pinfunction "1_1") (pintype "passive"))
    )
    (net (code "106") (name "Net-(Q27-PadC)") (class "Default")
      (node (ref "Q27") (pin "C") (pinfunction "C_C") (pintype "passive"))
      (node (ref "Q30") (pin "E") (pinfunction "E_E") (pintype "passive"))
      (node (ref "R59") (pin "2") (pinfunction "2_2") (pintype "passive"))
    )
    (net (code "107") (name "Net-(Q27-PadE)") (class "Default")
      (node (ref "Q27") (pin "E") (pinfunction "E_E") (pintype "passive"))
      (node (ref "R56") (pin "2") (pinfunction "2_2") (pintype "passive"))
    )
    (net (code "108") (name "Net-(Q28-PadE)") (class "Default")
      (node (ref "Q28") (pin "E") (pinfunction "E_E") (pintype "passive"))
      (node (ref "R57") (pin "2") (pinfunction "2_2") (pintype "passive"))
    )
    (net (code "109") (name "Net-(Q29-PadC)") (class "Default")
      (node (ref "Q29") (pin "C") (pinfunction "C_C") (pintype "passive"))
      (node (ref "Q33") (pin "C") (pinfunction "C_C") (pintype "passive"))
      (node (ref "Q36") (pin "B") (pinfunction "B_B") (pintype "passive"))
    )
    (net (code "110") (name "Net-(Q29-PadE)") (class "Default")
      (node (ref "Q29") (pin "E") (pinfunction "E_E") (pintype "passive"))
      (node (ref "Q30") (pin "C") (pinfunction "C_C") (pintype "passive"))
    )
    (net (code "111") (name "Net-(Q31-PadC)") (class "Default")
      (node (ref "Q31") (pin "C") (pinfunction "C_C") (pintype "passive"))
      (node (ref "Q32") (pin "E") (pinfunction "E_E") (pintype "passive"))
    )
    (net (code "112") (name "Net-(Q32-PadC)") (class "Default")
      (node (ref "Q32") (pin "C") (pinfunction "C_C") (pintype "passive"))
      (node (ref "Q34") (pin "C") (pinfunction "C_C") (pintype "passive"))
      (node (ref "Q37") (pin "B") (pinfunction "B_B") (pintype "passive"))
    )
    (net (code "113") (name "Net-(Q33-PadB)") (class "Default")
      (node (ref "Q33") (pin "B") (pinfunction "B_B") (pintype "passive"))
      (node (ref "Q35") (pin "B") (pinfunction "B_B") (pintype "passive"))
      (node (ref "Q35") (pin "C") (pinfunction "C_C") (pintype "passive"))
      (node (ref "Q36") (pin "E") (pinfunction "E_E") (pintype "passive"))
    )
    (net (code "114") (name "Net-(Q33-PadE)") (class "Default")
      (node (ref "Q33") (pin "E") (pinfunction "E_E") (pintype "passive"))
      (node (ref "R58") (pin "1") (pinfunction "1_1") (pintype "passive"))
    )
    (net (code "115") (name "Net-(Q34-PadB)") (class "Default")
      (node (ref "Q34") (pin "B") (pinfunction "B_B") (pintype "passive"))
      (node (ref "Q37") (pin "E") (pinfunction "E_E") (pintype "passive"))
      (node (ref "Q38") (pin "B") (pinfunction "B_B") (pintype "passive"))
      (node (ref "Q38") (pin "C") (pinfunction "C_C") (pintype "passive"))
    )
    (net (code "116") (name "Net-(Q34-PadE)") (class "Default")
      (node (ref "Q34") (pin "E") (pinfunction "E_E") (pintype "passive"))
      (node (ref "R61") (pin "2") (pinfunction "2_2") (pintype "passive"))
    )
    (net (code "117") (name "Net-(Q36-PadC)") (class "Default")
      (node (ref "Q36") (pin "C") (pinfunction "C_C") (pintype "passive"))
      (node (ref "Q39") (pin "E") (pinfunction "E_E") (pintype "passive"))
    )
    (net (code "118") (name "Net-(Q37-PadC)") (class "Default")
      (node (ref "Q37") (pin "C") (pinfunction "C_C") (pintype "passive"))
      (node (ref "Q40") (pin "E") (pinfunction "E_E") (pintype "passive"))
    )
    (net (code "119") (name "Net-(Q41-PadB)") (class "Default")
      (node (ref "Q41") (pin "B") (pinfunction "B_B") (pintype "passive"))
      (node (ref "Q41") (pin "C") (pinfunction "C_C") (pintype "passive"))
      (node (ref "Q43") (pin "B") (pinfunction "B_B") (pintype "passive"))
      (node (ref "R68") (pin "2") (pinfunction "2_2") (pintype "passive"))
    )
    (net (code "120") (name "Net-(Q41-PadE)") (class "Default")
      (node (ref "Q41") (pin "E") (pinfunction "E_E") (pintype "passive"))
      (node (ref "R67") (pin "1") (pinfunction "1_1") (pintype "passive"))
    )
    (net (code "121") (name "Net-(Q42-PadB)") (class "Default")
      (node (ref "Q42") (pin "B") (pinfunction "B_B") (pintype "passive"))
      (node (ref "Q42") (pin "C") (pinfunction "C_C") (pintype "passive"))
      (node (ref "Q44") (pin "B") (pinfunction "B_B") (pintype "passive"))
      (node (ref "R69") (pin "1") (pinfunction "1_1") (pintype "passive"))
    )
    (net (code "122") (name "Net-(Q42-PadE)") (class "Default")
      (node (ref "Q42") (pin "E") (pinfunction "E_E") (pintype "passive"))
      (node (ref "R70") (pin "2") (pinfunction "2_2") (pintype "passive"))
    )
    (net (code "123") (name "Net-(Q43-PadE)") (class "Default")
      (node (ref "Q43") (pin "E") (pinfunction "E_E") (pintype "passive"))
      (node (ref "R71") (pin "1") (pinfunction "1_1") (pintype "passive"))
    )
    (net (code "124") (name "Net-(Q44-PadE)") (class "Default")
      (node (ref "Q44") (pin "E") (pinfunction "E_E") (pintype "passive"))
      (node (ref "R72") (pin "2") (pinfunction "2_2") (pintype "passive"))
    )
    (net (code "125") (name "Net-(Q46-PadE)") (class "Default")
      (node (ref "Q46") (pin "E") (pinfunction "E_E") (pintype "passive"))
      (node (ref "Q48") (pin "B") (pinfunction "B_B") (pintype "passive"))
      (node (ref "R77") (pin "2") (pinfunction "2_2") (pintype "passive"))
    )
    (net (code "126") (name "Net-(Q47-PadE)") (class "Default")
      (node (ref "Q47") (pin "E") (pinfunction "E_E") (pintype "passive"))
      (node (ref "Q49") (pin "B") (pinfunction "B_B") (pintype "passive"))
      (node (ref "R77") (pin "1") (pinfunction "1_1") (pintype "passive"))
    )
    (net (code "127") (name "Net-(Q48-PadE)") (class "Default")
      (node (ref "Q48") (pin "E") (pinfunction "E_E") (pintype "passive"))
      (node (ref "Q50") (pin "B") (pinfunction "B_B") (pintype "passive"))
      (node (ref "R78") (pin "2") (pinfunction "2_2") (pintype "passive"))
    )
    (net (code "128") (name "Net-(Q49-PadE)") (class "Default")
      (node (ref "Q49") (pin "E") (pinfunction "E_E") (pintype "passive"))
      (node (ref "Q51") (pin "B") (pinfunction "B_B") (pintype "passive"))
      (node (ref "R78") (pin "1") (pinfunction "1_1") (pintype "passive"))
    )
    (net (code "129") (name "Net-(Q50-PadE)") (class "Default")
      (node (ref "Q50") (pin "E") (pinfunction "E_E") (pintype "passive"))
      (node (ref "R80") (pin "2") (pinfunction "2_2") (pintype "passive"))
    )
    (net (code "130") (name "Net-(Q51-PadE)") (class "Default")
      (node (ref "Q51") (pin "E") (pinfunction "E_E") (pintype "passive"))
      (node (ref "R81") (pin "1") (pinfunction "1_1") (pintype "passive"))
    )
    (net (code "131") (name "Net-(Q52-PadE)") (class "Default")
      (node (ref "Q52") (pin "E") (pinfunction "E_E") (pintype "passive"))
      (node (ref "R86") (pin "1") (pinfunction "1_1") (pintype "passive"))
    )
    (net (code "132") (name "Net-(Q53-PadC)") (class "Default")
      (node (ref "Q53") (pin "C") (pinfunction "C_C") (pintype "passive"))
      (node (ref "Q58") (pin "E") (pinfunction "E_E") (pintype "passive"))
      (node (ref "R92") (pin "1") (pinfunction "1_1") (pintype "passive"))
    )
    (net (code "133") (name "Net-(Q53-PadE)") (class "Default")
      (node (ref "Q53") (pin "E") (pinfunction "E_E") (pintype "passive"))
      (node (ref "R87") (pin "1") (pinfunction "1_1") (pintype "passive"))
    )
    (net (code "134") (name "Net-(Q54-PadC)") (class "Default")
      (node (ref "Q54") (pin "C") (pinfunction "C_C") (pintype "passive"))
      (node (ref "Q57") (pin "E") (pinfunction "E_E") (pintype "passive"))
      (node (ref "R91") (pin "2") (pinfunction "2_2") (pintype "passive"))
    )
    (net (code "135") (name "Net-(Q54-PadE)") (class "Default")
      (node (ref "Q54") (pin "E") (pinfunction "E_E") (pintype "passive"))
      (node (ref "R88") (pin "2") (pinfunction "2_2") (pintype "passive"))
    )
    (net (code "136") (name "Net-(Q55-PadE)") (class "Default")
      (node (ref "Q55") (pin "E") (pinfunction "E_E") (pintype "passive"))
      (node (ref "R89") (pin "2") (pinfunction "2_2") (pintype "passive"))
    )
    (net (code "137") (name "Net-(Q56-PadC)") (class "Default")
      (node (ref "Q56") (pin "C") (pinfunction "C_C") (pintype "passive"))
      (node (ref "Q60") (pin "C") (pinfunction "C_C") (pintype "passive"))
      (node (ref "Q63") (pin "B") (pinfunction "B_B") (pintype "passive"))
    )
    (net (code "138") (name "Net-(Q56-PadE)") (class "Default")
      (node (ref "Q56") (pin "E") (pinfunction "E_E") (pintype "passive"))
      (node (ref "Q57") (pin "C") (pinfunction "C_C") (pintype "passive"))
    )
    (net (code "139") (name "Net-(Q58-PadC)") (class "Default")
      (node (ref "Q58") (pin "C") (pinfunction "C_C") (pintype "passive"))
      (node (ref "Q59") (pin "E") (pinfunction "E_E") (pintype "passive"))
    )
    (net (code "140") (name "Net-(Q59-PadC)") (class "Default")
      (node (ref "Q59") (pin "C") (pinfunction "C_C") (pintype "passive"))
      (node (ref "Q61") (pin "C") (pinfunction "C_C") (pintype "passive"))
      (node (ref "Q64") (pin "B") (pinfunction "B_B") (pintype "passive"))
    )
    (net (code "141") (name "Net-(Q60-PadB)") (class "Default")
      (node (ref "Q60") (pin "B") (pinfunction "B_B") (pintype "passive"))
      (node (ref "Q62") (pin "B") (pinfunction "B_B") (pintype "passive"))
      (node (ref "Q62") (pin "C") (pinfunction "C_C") (pintype "passive"))
      (node (ref "Q63") (pin "E") (pinfunction "E_E") (pintype "passive"))
    )
    (net (code "142") (name "Net-(Q60-PadE)") (class "Default")
      (node (ref "Q60") (pin "E") (pinfunction "E_E") (pintype "passive"))
      (node (ref "R90") (pin "1") (pinfunction "1_1") (pintype "passive"))
    )
    (net (code "143") (name "Net-(Q61-PadB)") (class "Default")
      (node (ref "Q61") (pin "B") (pinfunction "B_B") (pintype "passive"))
      (node (ref "Q64") (pin "E") (pinfunction "E_E") (pintype "passive"))
      (node (ref "Q65") (pin "B") (pinfunction "B_B") (pintype "passive"))
      (node (ref "Q65") (pin "C") (pinfunction "C_C") (pintype "passive"))
    )
    (net (code "144") (name "Net-(Q61-PadE)") (class "Default")
      (node (ref "Q61") (pin "E") (pinfunction "E_E") (pintype "passive"))
      (node (ref "R93") (pin "2") (pinfunction "2_2") (pintype "passive"))
    )
    (net (code "145") (name "Net-(Q63-PadC)") (class "Default")
      (node (ref "Q63") (pin "C") (pinfunction "C_C") (pintype "passive"))
      (node (ref "Q66") (pin "E") (pinfunction "E_E") (pintype "passive"))
    )
    (net (code "146") (name "Net-(Q64-PadC)") (class "Default")
      (node (ref "Q64") (pin "C") (pinfunction "C_C") (pintype "passive"))
      (node (ref "Q67") (pin "E") (pinfunction "E_E") (pintype "passive"))
    )
    (net (code "147") (name "Net-(Q68-PadB)") (class "Default")
      (node (ref "Q68") (pin "B") (pinfunction "B_B") (pintype "passive"))
      (node (ref "Q68") (pin "C") (pinfunction "C_C") (pintype "passive"))
      (node (ref "Q70") (pin "B") (pinfunction "B_B") (pintype "passive"))
      (node (ref "R100") (pin "2") (pinfunction "2_2") (pintype "passive"))
    )
    (net (code "148") (name "Net-(Q68-PadE)") (class "Default")
      (node (ref "Q68") (pin "E") (pinfunction "E_E") (pintype "passive"))
      (node (ref "R99") (pin "1") (pinfunction "1_1") (pintype "passive"))
    )
    (net (code "149") (name "Net-(Q69-PadB)") (class "Default")
      (node (ref "Q69") (pin "B") (pinfunction "B_B") (pintype "passive"))
      (node (ref "Q69") (pin "C") (pinfunction "C_C") (pintype "passive"))
      (node (ref "Q71") (pin "B") (pinfunction "B_B") (pintype "passive"))
      (node (ref "R101") (pin "1") (pinfunction "1_1") (pintype "passive"))
    )
    (net (code "150") (name "Net-(Q69-PadE)") (class "Default")
      (node (ref "Q69") (pin "E") (pinfunction "E_E") (pintype "passive"))
      (node (ref "R102") (pin "2") (pinfunction "2_2") (pintype "passive"))
    )
    (net (code "151") (name "Net-(Q70-PadE)") (class "Default")
      (node (ref "Q70") (pin "E") (pinfunction "E_E") (pintype "passive"))
      (node (ref "R103") (pin "1") (pinfunction "1_1") (pintype "passive"))
    )
    (net (code "152") (name "Net-(Q71-PadE)") (class "Default")
      (node (ref "Q71") (pin "E") (pinfunction "E_E") (pintype "passive"))
      (node (ref "R104") (pin "2") (pinfunction "2_2") (pintype "passive"))
    )
    (net (code "153") (name "Net-(Q73-PadE)") (class "Default")
      (node (ref "Q73") (pin "E") (pinfunction "E_E") (pintype "passive"))
      (node (ref "Q75") (pin "B") (pinfunction "B_B") (pintype "passive"))
      (node (ref "R109") (pin "2") (pinfunction "2_2") (pintype "passive"))
    )
    (net (code "154") (name "Net-(Q74-PadE)") (class "Default")
      (node (ref "Q74") (pin "E") (pinfunction "E_E") (pintype "passive"))
      (node (ref "Q76") (pin "B") (pinfunction "B_B") (pintype "passive"))
      (node (ref "R109") (pin "1") (pinfunction "1_1") (pintype "passive"))
    )
    (net (code "155") (name "Net-(Q75-PadE)") (class "Default")
      (node (ref "Q75") (pin "E") (pinfunction "E_E") (pintype "passive"))
      (node (ref "Q77") (pin "B") (pinfunction "B_B") (pintype "passive"))
      (node (ref "R110") (pin "2") (pinfunction "2_2") (pintype "passive"))
    )
    (net (code "156") (name "Net-(Q76-PadE)") (class "Default")
      (node (ref "Q76") (pin "E") (pinfunction "E_E") (pintype "passive"))
      (node (ref "Q78") (pin "B") (pinfunction "B_B") (pintype "passive"))
      (node (ref "R110") (pin "1") (pinfunction "1_1") (pintype "passive"))
    )
    (net (code "157") (name "Net-(Q77-PadE)") (class "Default")
      (node (ref "Q77") (pin "E") (pinfunction "E_E") (pintype "passive"))
      (node (ref "R112") (pin "2") (pinfunction "2_2") (pintype "passive"))
    )
    (net (code "158") (name "Net-(Q78-PadE)") (class "Default")
      (node (ref "Q78") (pin "E") (pinfunction "E_E") (pintype "passive"))
      (node (ref "R113") (pin "1") (pinfunction "1_1") (pintype "passive"))
    )
    (net (code "159") (name "Net-(R59-Pad1)") (class "Default")
      (node (ref "R59") (pin "1") (pinfunction "1_1") (pintype "passive"))
      (node (ref "R60") (pin "2") (pinfunction "2_2") (pintype "passive"))
      (node (ref "R63") (pin "2") (pinfunction "2_2") (pintype "passive"))
      (node (ref "R66") (pin "1") (pinfunction "1_1") (pintype "passive"))
    )
    (net (code "160") (name "Net-(R74-A)") (class "Default")
      (node (ref "C18") (pin "2") (pinfunction "2_2") (pintype "passive"))
      (node (ref "C20") (pin "1") (pinfunction "1_1") (pintype "passive"))
      (node (ref "Q40") (pin "C") (pinfunction "C_C") (pintype "passive"))
      (node (ref "Q44") (pin "C") (pinfunction "C_C") (pintype "passive"))
      (node (ref "Q45") (pin "E") (pinfunction "E_E") (pintype "passive"))
      (node (ref "Q47") (pin "B") (pinfunction "B_B") (pintype "passive"))
      (node (ref "R74") (pin "1") (pinfunction "A_1") (pintype "passive"))
      (node (ref "R74") (pin "2") (pinfunction "S_2") (pintype "passive"))
      (node (ref "R76") (pin "2") (pinfunction "2_2") (pintype "passive"))
    )
    (net (code "161") (name "Net-(R74-E)") (class "Default")
      (node (ref "Q45") (pin "B") (pinfunction "B_B") (pintype "passive"))
      (node (ref "R73") (pin "1") (pinfunction "1_1") (pintype "passive"))
      (node (ref "R74") (pin "3") (pinfunction "E_3") (pintype "passive"))
    )
    (net (code "162") (name "Net-(R91-Pad1)") (class "Default")
      (node (ref "R91") (pin "1") (pinfunction "1_1") (pintype "passive"))
      (node (ref "R92") (pin "2") (pinfunction "2_2") (pintype "passive"))
      (node (ref "R95") (pin "2") (pinfunction "2_2") (pintype "passive"))
      (node (ref "R98") (pin "1") (pinfunction "1_1") (pintype "passive"))
    )
    (net (code "163") (name "Net-(R106-A)") (class "Default")
      (node (ref "C28") (pin "2") (pinfunction "2_2") (pintype "passive"))
      (node (ref "C30") (pin "1") (pinfunction "1_1") (pintype "passive"))
      (node (ref "Q67") (pin "C") (pinfunction "C_C") (pintype "passive"))
      (node (ref "Q71") (pin "C") (pinfunction "C_C") (pintype "passive"))
      (node (ref "Q72") (pin "E") (pinfunction "E_E") (pintype "passive"))
      (node (ref "Q74") (pin "B") (pinfunction "B_B") (pintype "passive"))
      (node (ref "R106") (pin "1") (pinfunction "A_1") (pintype "passive"))
      (node (ref "R106") (pin "2") (pinfunction "S_2") (pintype "passive"))
      (node (ref "R108") (pin "2") (pinfunction "2_2") (pintype "passive"))
    )
    (net (code "164") (name "Net-(R106-E)") (class "Default")
      (node (ref "Q72") (pin "B") (pinfunction "B_B") (pintype "passive"))
      (node (ref "R105") (pin "1") (pinfunction "1_1") (pintype "passive"))
      (node (ref "R106") (pin "3") (pinfunction "E_3") (pintype "passive"))
    )
    (net (code "165") (name "Net-(U$5-BUF)") (class "Default")
      (node (ref "R138") (pin "2") (pinfunction "2_2") (pintype "passive"))
      (node (ref "U$5") (pin "8") (pinfunction "BUF_8") (pintype "bidirectional"))
    )
    (net (code "166") (name "Net-(U$5-EN)") (class "Default")
      (node (ref "SJ1") (pin "1") (pinfunction "1_1") (pintype "passive"))
      (node (ref "U$5") (pin "2") (pinfunction "EN_2") (pintype "bidirectional"))
    )
    (net (code "167") (name "Net-(U$5-FB+)") (class "Default")
      (node (ref "C71") (pin "2") (pinfunction "2_2") (pintype "passive"))
      (node (ref "R136") (pin "1") (pinfunction "1_1") (pintype "passive"))
      (node (ref "R137") (pin "2") (pinfunction "2_2") (pintype "passive"))
      (node (ref "U$5") (pin "9") (pinfunction "FB+_9") (pintype "bidirectional"))
    )
    (net (code "168") (name "Net-(U$5-FB-)") (class "Default")
      (node (ref "C72") (pin "1") (pinfunction "1_1") (pintype "passive"))
      (node (ref "R138") (pin "1") (pinfunction "1_1") (pintype "passive"))
      (node (ref "R139") (pin "2") (pinfunction "2_2") (pintype "passive"))
      (node (ref "U$5") (pin "7") (pinfunction "FB-_7") (pintype "bidirectional"))
    )
    (net (code "169") (name "Net-(U$5-NR{slash}SS)") (class "Default")
      (node (ref "C2") (pin "1") (pinfunction "1_1") (pintype "passive"))
      (node (ref "U$5") (pin "3") (pinfunction "NR/SS_3") (pintype "bidirectional"))
    )
    (net (code "170") (name "OUT+") (class "Default")
      (node (ref "C1") (pin "1") (pinfunction "1_1") (pintype "passive"))
      (node (ref "PAD1") (pin "P$1") (pinfunction "P$1_P$1") (pintype "bidirectional"))
      (node (ref "R66") (pin "2") (pinfunction "2_2") (pintype "passive"))
      (node (ref "R80") (pin "1") (pinfunction "1_1") (pintype "passive"))
      (node (ref "R81") (pin "2") (pinfunction "2_2") (pintype "passive"))
      (node (ref "R82") (pin "1") (pinfunction "1_1") (pintype "passive"))
    )
    (net (code "171") (name "OUT-") (class "Default")
      (node (ref "PAD2") (pin "P$1") (pinfunction "P$1_P$1") (pintype "bidirectional"))
      (node (ref "R112") (pin "1") (pinfunction "1_1") (pintype "passive"))
      (node (ref "R113") (pin "2") (pinfunction "2_2") (pintype "passive"))
      (node (ref "R114") (pin "1") (pinfunction "1_1") (pintype "passive"))
      (node (ref "R133") (pin "2") (pinfunction "2_2") (pintype "passive"))
      (node (ref "R98") (pin "2") (pinfunction "2_2") (pintype "passive"))
    )
    (net (code "172") (name "UOUT+") (class "Default")
      (node (ref "Q10") (pin "B") (pinfunction "B_B") (pintype "passive"))
      (node (ref "Q5") (pin "6") (pinfunction "C_6") (pintype "passive"))
      (node (ref "Q6") (pin "6") (pinfunction "C_6") (pintype "passive"))
      (node (ref "Q9") (pin "B") (pinfunction "B_B") (pintype "passive"))
      (node (ref "R11") (pin "2") (pinfunction "2_2") (pintype "passive"))
      (node (ref "R21") (pin "2") (pinfunction "2_2") (pintype "passive"))
    )
    (net (code "173") (name "UOUT-") (class "Default")
      (node (ref "Q17") (pin "B") (pinfunction "B_B") (pintype "passive"))
      (node (ref "Q18") (pin "B") (pinfunction "B_B") (pintype "passive"))
      (node (ref "Q5") (pin "4") (pinfunction "C_4") (pintype "passive"))
      (node (ref "Q6") (pin "4") (pinfunction "C_4") (pintype "passive"))
      (node (ref "R20") (pin "2") (pinfunction "2_2") (pintype "passive"))
      (node (ref "R36") (pin "2") (pinfunction "2_2") (pintype "passive"))
    )
    (net (code "174") (name "V+") (class "Default")
      (node (ref "C11") (pin "1") (pinfunction "1_1") (pintype "passive"))
      (node (ref "C25") (pin "+") (pinfunction "+_+") (pintype "passive"))
      (node (ref "C35") (pin "+") (pinfunction "+_+") (pintype "passive"))
      (node (ref "C5") (pin "+") (pinfunction "+_+") (pintype "passive"))
      (node (ref "C66") (pin "1") (pinfunction "1_1") (pintype "passive"))
      (node (ref "C68") (pin "1") (pinfunction "1_1") (pintype "passive"))
      (node (ref "C7") (pin "+") (pinfunction "+_+") (pintype "passive"))
      (node (ref "C74") (pin "1") (pinfunction "1_1") (pintype "passive"))
      (node (ref "C9") (pin "1") (pinfunction "1_1") (pintype "passive"))
      (node (ref "D1") (pin "A") (pinfunction "A_A") (pintype "passive"))
      (node (ref "D7") (pin "A") (pinfunction "A_A") (pintype "passive"))
      (node (ref "LED1") (pin "A") (pinfunction "A_A") (pintype "passive"))
      (node (ref "LED3") (pin "A") (pinfunction "A_A") (pintype "passive"))
      (node (ref "LED5") (pin "A") (pinfunction "A_A") (pintype "passive"))
      (node (ref "LED7") (pin "A") (pinfunction "A_A") (pintype "passive"))
      (node (ref "Q13") (pin "C") (pinfunction "C_C") (pintype "passive"))
      (node (ref "Q15") (pin "C") (pinfunction "C_C") (pintype "passive"))
      (node (ref "Q17") (pin "C") (pinfunction "C_C") (pintype "passive"))
      (node (ref "Q21") (pin "C") (pinfunction "C_C") (pintype "passive"))
      (node (ref "Q23") (pin "C") (pinfunction "C_C") (pintype "passive"))
      (node (ref "Q46") (pin "C") (pinfunction "C_C") (pintype "passive"))
      (node (ref "Q48") (pin "C") (pinfunction "C_C") (pintype "passive"))
      (node (ref "Q50") (pin "C") (pinfunction "C_C") (pintype "passive"))
      (node (ref "Q73") (pin "C") (pinfunction "C_C") (pintype "passive"))
      (node (ref "Q75") (pin "C") (pinfunction "C_C") (pintype "passive"))
      (node (ref "Q77") (pin "C") (pinfunction "C_C") (pintype "passive"))
      (node (ref "Q9") (pin "C") (pinfunction "C_C") (pintype "passive"))
      (node (ref "R103") (pin "2") (pinfunction "2_2") (pintype "passive"))
      (node (ref "R12") (pin "2") (pinfunction "2_2") (pintype "passive"))
      (node (ref "R131") (pin "2") (pinfunction "2_2") (pintype "passive"))
      (node (ref "R141") (pin "2") (pinfunction "2_2") (pintype "passive"))
      (node (ref "R18") (pin "2") (pinfunction "2_2") (pintype "passive"))
      (node (ref "R23") (pin "2") (pinfunction "2_2") (pintype "passive"))
      (node (ref "R38") (pin "2") (pinfunction "2_2") (pintype "passive"))
      (node (ref "R5") (pin "2") (pinfunction "2_2") (pintype "passive"))
      (node (ref "R54") (pin "2") (pinfunction "2_2") (pintype "passive"))
      (node (ref "R58") (pin "2") (pinfunction "2_2") (pintype "passive"))
      (node (ref "R62") (pin "2") (pinfunction "2_2") (pintype "passive"))
      (node (ref "R67") (pin "2") (pinfunction "2_2") (pintype "passive"))
      (node (ref "R71") (pin "2") (pinfunction "2_2") (pintype "passive"))
      (node (ref "R86") (pin "2") (pinfunction "2_2") (pintype "passive"))
      (node (ref "R90") (pin "2") (pinfunction "2_2") (pintype "passive"))
      (node (ref "R94") (pin "2") (pinfunction "2_2") (pintype "passive"))
      (node (ref "R99") (pin "2") (pinfunction "2_2") (pintype "passive"))
      (node (ref "SJ1") (pin "2") (pinfunction "2_2") (pintype "passive"))
      (node (ref "U$5") (pin "1") (pinfunction "IN+_1") (pintype "bidirectional"))
    )
    (net (code "175") (name "V-") (class "Default")
      (node (ref "C10") (pin "2") (pinfunction "2_2") (pintype "passive"))
      (node (ref "C12") (pin "2") (pinfunction "2_2") (pintype "passive"))
      (node (ref "C26") (pin "-") (pinfunction "-_-") (pintype "passive"))
      (node (ref "C36") (pin "-") (pinfunction "-_-") (pintype "passive"))
      (node (ref "C6") (pin "-") (pinfunction "-_-") (pintype "passive"))
      (node (ref "C65") (pin "1") (pinfunction "1_1") (pintype "passive"))
      (node (ref "C67") (pin "1") (pinfunction "1_1") (pintype "passive"))
      (node (ref "C75") (pin "2") (pinfunction "2_2") (pintype "passive"))
      (node (ref "C8") (pin "-") (pinfunction "-_-") (pintype "passive"))
      (node (ref "D10") (pin "C") (pinfunction "C_C") (pintype "passive"))
      (node (ref "D4") (pin "C") (pinfunction "C_C") (pintype "passive"))
      (node (ref "LED2") (pin "C") (pinfunction "C_C") (pintype "passive"))
      (node (ref "LED4") (pin "C") (pinfunction "C_C") (pintype "passive"))
      (node (ref "LED6") (pin "C") (pinfunction "C_C") (pintype "passive"))
      (node (ref "LED8") (pin "C") (pinfunction "C_C") (pintype "passive"))
      (node (ref "Q10") (pin "C") (pinfunction "C_C") (pintype "passive"))
      (node (ref "Q14") (pin "C") (pinfunction "C_C") (pintype "passive"))
      (node (ref "Q16") (pin "C") (pinfunction "C_C") (pintype "passive"))
      (node (ref "Q18") (pin "C") (pinfunction "C_C") (pintype "passive"))
      (node (ref "Q22") (pin "C") (pinfunction "C_C") (pintype "passive"))
      (node (ref "Q24") (pin "C") (pinfunction "C_C") (pintype "passive"))
      (node (ref "Q47") (pin "C") (pinfunction "C_C") (pintype "passive"))
      (node (ref "Q49") (pin "C") (pinfunction "C_C") (pintype "passive"))
      (node (ref "Q51") (pin "C") (pinfunction "C_C") (pintype "passive"))
      (node (ref "Q74") (pin "C") (pinfunction "C_C") (pintype "passive"))
      (node (ref "Q76") (pin "C") (pinfunction "C_C") (pintype "passive"))
      (node (ref "Q78") (pin "C") (pinfunction "C_C") (pintype "passive"))
      (node (ref "R102") (pin "1") (pinfunction "1_1") (pintype "passive"))
      (node (ref "R104") (pin "1") (pinfunction "1_1") (pintype "passive"))
      (node (ref "R13") (pin "1") (pinfunction "1_1") (pintype "passive"))
      (node (ref "R132") (pin "1") (pinfunction "1_1") (pintype "passive"))
      (node (ref "R140") (pin "2") (pinfunction "2_2") (pintype "passive"))
      (node (ref "R19") (pin "1") (pinfunction "1_1") (pintype "passive"))
      (node (ref "R26") (pin "1") (pinfunction "1_1") (pintype "passive"))
      (node (ref "R41") (pin "1") (pinfunction "1_1") (pintype "passive"))
      (node (ref "R57") (pin "1") (pinfunction "1_1") (pintype "passive"))
      (node (ref "R61") (pin "1") (pinfunction "1_1") (pintype "passive"))
      (node (ref "R64") (pin "1") (pinfunction "1_1") (pintype "passive"))
      (node (ref "R7") (pin "1") (pinfunction "1_1") (pintype "passive"))
      (node (ref "R70") (pin "1") (pinfunction "1_1") (pintype "passive"))
      (node (ref "R72") (pin "1") (pinfunction "1_1") (pintype "passive"))
      (node (ref "R89") (pin "1") (pinfunction "1_1") (pintype "passive"))
      (node (ref "R93") (pin "1") (pinfunction "1_1") (pintype "passive"))
      (node (ref "R96") (pin "1") (pinfunction "1_1") (pintype "passive"))
      (node (ref "U$5") (pin "5") (pinfunction "IN-_5") (pintype "bidirectional"))
    )
    (net (code "176") (name "unconnected-(H1-PadP$1)") (class "Default")
      (node (ref "H1") (pin "P$1") (pinfunction "P$1_P$1") (pintype "bidirectional"))
    )
    (net (code "177") (name "unconnected-(H2-PadP$1)") (class "Default")
      (node (ref "H2") (pin "P$1") (pinfunction "P$1_P$1") (pintype "bidirectional"))
    )
    (net (code "178") (name "unconnected-(H3-PadP$1)") (class "Default")
      (node (ref "H3") (pin "P$1") (pinfunction "P$1_P$1") (pintype "bidirectional"))
    )
    (net (code "179") (name "unconnected-(H4-PadP$1)") (class "Default")
      (node (ref "H4") (pin "P$1") (pinfunction "P$1_P$1") (pintype "bidirectional"))
    )
    (net (code "180") (name "unconnected-(H5-PadP$1)") (class "Default")
      (node (ref "H5") (pin "P$1") (pinfunction "P$1_P$1") (pintype "bidirectional"))
    )
    (net (code "181") (name "unconnected-(H6-PadP$1)") (class "Default")
      (node (ref "H6") (pin "P$1") (pinfunction "P$1_P$1") (pintype "bidirectional"))
    )
    (net (code "182") (name "unconnected-(H7-PadP$1)") (class "Default")
      (node (ref "H7") (pin "P$1") (pinfunction "P$1_P$1") (pintype "bidirectional"))
    )
    (net (code "183") (name "unconnected-(H8-PadP$1)") (class "Default")
      (node (ref "H8") (pin "P$1") (pinfunction "P$1_P$1") (pintype "bidirectional"))
    )
    (net (code "184") (name "unconnected-(IC1-CMP1-Pad1)") (class "Default")
      (node (ref "IC1") (pin "1") (pinfunction "CMP1_1") (pintype "passive"))
    )
    (net (code "185") (name "unconnected-(IC2-CMP1-Pad1)") (class "Default")
      (node (ref "IC2") (pin "1") (pinfunction "CMP1_1") (pintype "passive"))
    )
    (net (code "186") (name "unconnected-(IC3-CMP1-Pad1)") (class "Default")
      (node (ref "IC3") (pin "1") (pinfunction "CMP1_1") (pintype "passive"))
    )
    (net (code "187") (name "unconnected-(IC3-CMP2-Pad8)") (class "Default")
      (node (ref "IC3") (pin "8") (pinfunction "CMP2_8") (pintype "passive"))
    )
    (net (code "188") (name "unconnected-(IC4-CMP1-Pad1)") (class "Default")
      (node (ref "IC4") (pin "1") (pinfunction "CMP1_1") (pintype "passive"))
    )
    (net (code "189") (name "unconnected-(IC4-CMP2-Pad8)") (class "Default")
      (node (ref "IC4") (pin "8") (pinfunction "CMP2_8") (pintype "passive"))
    )
  )
)
